# Power.net
KiCad netlist of a schematic drawn in Altium Designer
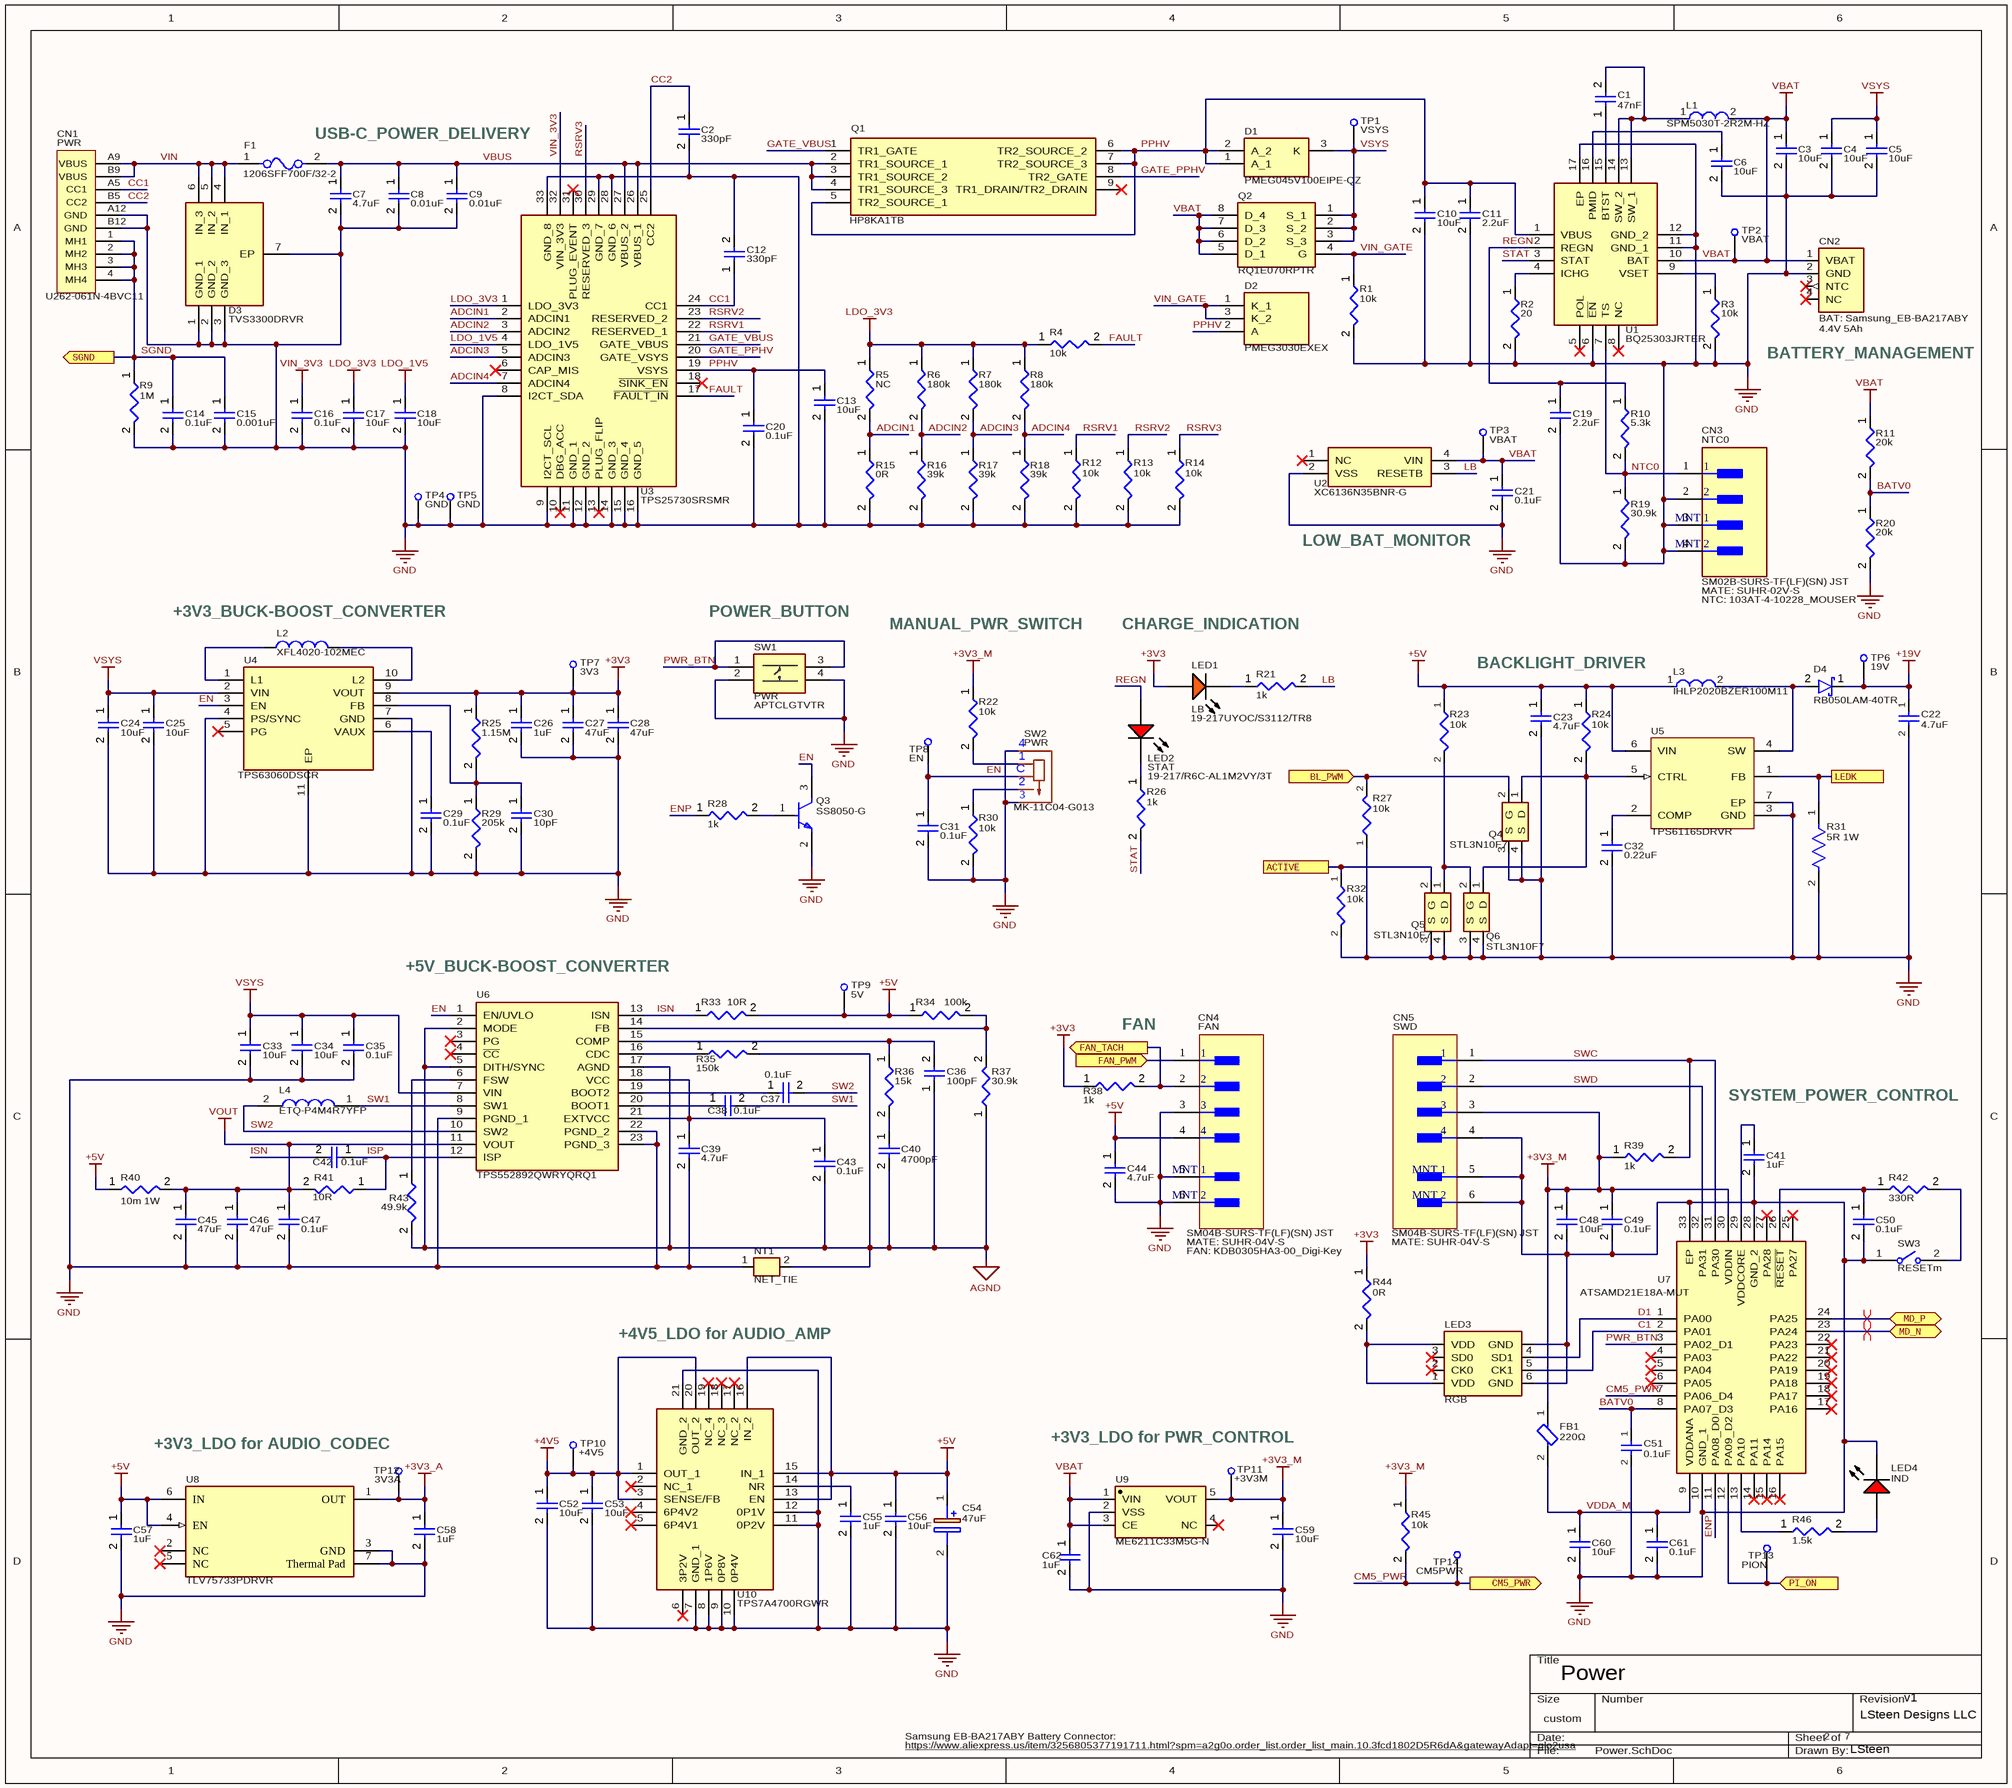
[diagram p0: Power.SchDoc]

(export (version "E")
  (design (tool "Eeschema 10.0.6"))
  (components
    (comp (ref "C1")
      (value "47nF")
      (footprint "CAPC1005X56X25LL10T15")
      (description "Chip Capacitor, 47 nF, +/- 5%, 16 V, 0402 (1005 Metric)")
      (fields (field (name "TOLERANCE") "5%"))
      (libsource (lib "Colorado Technical University") (part "CAP-NP-2"))
    )
    (comp (ref "C2")
      (value "330pF")
      (footprint "CAPC1005X56X25LL10T15")
      (description "Chip Capacitor, 330pF, +/- 5%, 16 V, 0402 (1005 Metric)")
      (fields (field (name "TOLERANCE") "5%"))
      (libsource (lib "Colorado Technical University") (part "CAP-NP-2"))
    )
    (comp (ref "C3")
      (value "10uF")
      (footprint "CAPC0805(2012)145_L")
      (description "Chip Capacitor, 10µF +/-20%, 25V, 0805, Thickness 1.45 mm")
      (fields (field (name "TOLERANCE") "10%"))
      (libsource (lib "Colorado Technical University") (part "CAP-NP-2"))
    )
    (comp (ref "C4")
      (value "10uF")
      (footprint "CAPC0805(2012)145_L")
      (description "Chip Capacitor, 10µF +/-20%, 25V, 0805, Thickness 1.45 mm")
      (fields (field (name "TOLERANCE") "10%"))
      (libsource (lib "Colorado Technical University") (part "CAP-NP-2"))
    )
    (comp (ref "C5")
      (value "10uF")
      (footprint "CAPC0805(2012)145_L")
      (description "Chip Capacitor, 10µF +/-20%, 25V, 0805, Thickness 1.45 mm")
      (fields (field (name "TOLERANCE") "10%"))
      (libsource (lib "Colorado Technical University") (part "CAP-NP-2"))
    )
    (comp (ref "C6")
      (value "10uF")
      (footprint "CAPC0805(2012)145_L")
      (description "Chip Capacitor, 10µF +/-20%, 25V, 0805, Thickness 1.45 mm")
      (fields (field (name "TOLERANCE") "10%"))
      (libsource (lib "Colorado Technical University") (part "CAP-NP-2"))
    )
    (comp (ref "C7")
      (value "4.7uF")
      (footprint "CAPC0603(1608)100_L")
      (description "Chip Capacitor, 4.7uF +/-20%, 10V, 0603, Thickness 1 mm")
      (fields (field (name "TOLERANCE") "10%"))
      (libsource (lib "Colorado Technical University") (part "CAP-NP-2"))
    )
    (comp (ref "C8")
      (value "0.01uF")
      (footprint "CAPC1005X56X25LL10T15")
      (description "Chip Capacitor, 0.01 uF, +/- 5%, 16 V, 0402 (1005 Metric)")
      (fields (field (name "TOLERANCE") "5%"))
      (libsource (lib "Colorado Technical University") (part "CAP-NP-2"))
    )
    (comp (ref "C9")
      (value "0.01uF")
      (footprint "CAPC1005X56X25LL10T15")
      (description "Chip Capacitor, 0.01 uF, +/- 5%, 16 V, 0402 (1005 Metric)")
      (fields (field (name "TOLERANCE") "5%"))
      (libsource (lib "Colorado Technical University") (part "CAP-NP-2"))
    )
    (comp (ref "C10")
      (value "10uF")
      (footprint "CAPC0805(2012)145_L")
      (description "Chip Capacitor, 10µF +/-20%, 25V, 0805, Thickness 1.45 mm")
      (fields (field (name "TOLERANCE") "10%"))
      (libsource (lib "Colorado Technical University") (part "CAP-NP-2"))
    )
    (comp (ref "C11")
      (value "2.2uF")
      (footprint "CAPC0603(1608)100_L")
      (description "Chip Capacitor, 2.2uF +/-20%, 10V, 0603, Thickness 1 mm")
      (fields (field (name "TOLERANCE") "10%"))
      (libsource (lib "Colorado Technical University") (part "CAP-NP-2"))
    )
    (comp (ref "C12")
      (value "330pF")
      (footprint "CAPC1005X56X25LL10T15")
      (description "Chip Capacitor, 330pF, +/- 5%, 16 V, 0402 (1005 Metric)")
      (fields (field (name "TOLERANCE") "5%"))
      (libsource (lib "Colorado Technical University") (part "CAP-NP-2"))
    )
    (comp (ref "C13")
      (value "10uF")
      (footprint "CAPC0603(1608)100_L")
      (description "Chip Capacitor, 10uF +/-20%, 10V, 0603, Thickness 1 mm")
      (fields (field (name "TOLERANCE") "10%"))
      (libsource (lib "Colorado Technical University") (part "CAP-NP-2"))
    )
    (comp (ref "C14")
      (value "0.1uF")
      (footprint "CAPC1005X56X25LL10T15")
      (description "Chip Capacitor, 0.1 uF, +/- 5%, 16 V, 0402 (1005 Metric)")
      (fields (field (name "TOLERANCE") "5%"))
      (libsource (lib "Colorado Technical University") (part "CAP-NP-2"))
    )
    (comp (ref "C15")
      (value "0.001uF")
      (footprint "CAPC1005X56X25LL10T15")
      (description "Chip Capacitor, 0.1 uF, +/- 5%, 16 V, 0402 (1005 Metric)")
      (fields (field (name "TOLERANCE") "5%"))
      (libsource (lib "Colorado Technical University") (part "CAP-NP-2"))
    )
    (comp (ref "C16")
      (value "0.1uF")
      (footprint "CAPC1005X56X25LL10T15")
      (description "Chip Capacitor, 0.1 uF, +/- 5%, 16 V, 0402 (1005 Metric)")
      (fields (field (name "TOLERANCE") "5%"))
      (libsource (lib "Colorado Technical University") (part "CAP-NP-2"))
    )
    (comp (ref "C17")
      (value "10uF")
      (footprint "CAPC0603(1608)100_L")
      (description "Chip Capacitor, 10uF +/-20%, 10V, 0603, Thickness 1 mm")
      (fields (field (name "TOLERANCE") "10%"))
      (libsource (lib "Colorado Technical University") (part "CAP-NP-2"))
    )
    (comp (ref "C18")
      (value "10uF")
      (footprint "CAPC0603(1608)100_L")
      (description "Chip Capacitor, 10uF +/-20%, 10V, 0603, Thickness 1 mm")
      (fields (field (name "TOLERANCE") "10%"))
      (libsource (lib "Colorado Technical University") (part "CAP-NP-2"))
    )
    (comp (ref "C19")
      (value "2.2uF")
      (footprint "CAPC1005X56X25LL10T15")
      (description "Chip Capacitor, 2.2uF uF, +/- 5%, 16 V, 0402 (1005 Metric)")
      (fields (field (name "TOLERANCE") "5%"))
      (libsource (lib "Colorado Technical University") (part "CAP-NP-2"))
    )
    (comp (ref "C20")
      (value "0.1uF")
      (footprint "CAPC1005X56X25LL10T15")
      (description "Chip Capacitor, 0.1 uF, +/- 5%, 16 V, 0402 (1005 Metric)")
      (fields (field (name "TOLERANCE") "5%"))
      (libsource (lib "Colorado Technical University") (part "CAP-NP-2"))
    )
    (comp (ref "C21")
      (value "0.1uF")
      (footprint "CAPC1005X56X25LL10T15")
      (description "Chip Capacitor, 0.1 uF, +/- 5%, 16 V, 0402 (1005 Metric)")
      (fields (field (name "TOLERANCE") "5%"))
      (libsource (lib "Colorado Technical University") (part "CAP-NP-2"))
    )
    (comp (ref "C22")
      (value "4.7uF")
      (footprint "SamacSys:CAPC2012X140N")
      (description "C0805")
      (libsource (lib "SamacSys") (part "C0805"))
    )
    (comp (ref "C23")
      (value "4.7uF")
      (footprint "CAPC0805(2012)145_L")
      (description "Chip Capacitor, 4.7µF +/-20%, 25V, 0805, Thickness 1.45 mm")
      (fields (field (name "TOLERANCE") "10%"))
      (libsource (lib "Colorado Technical University") (part "CAP-NP-2"))
    )
    (comp (ref "C24")
      (value "10uF")
      (footprint "CAPC0603(1608)100_L")
      (description "Chip Capacitor, 10uF +/-20%, 10V, 0603, Thickness 1 mm")
      (fields (field (name "TOLERANCE") "10%"))
      (libsource (lib "Colorado Technical University") (part "CAP-NP-2"))
    )
    (comp (ref "C25")
      (value "10uF")
      (footprint "CAPC0603(1608)100_L")
      (description "Chip Capacitor, 10uF +/-20%, 10V, 0603, Thickness 1 mm")
      (fields (field (name "TOLERANCE") "10%"))
      (libsource (lib "Colorado Technical University") (part "CAP-NP-2"))
    )
    (comp (ref "C26")
      (value "1uF")
      (footprint "CAPC1005X56X25LL10T15")
      (description "Chip Capacitor, 1 uF, +/- 5%, 16 V, 0402 (1005 Metric)")
      (fields (field (name "TOLERANCE") "5%"))
      (libsource (lib "Colorado Technical University") (part "CAP-NP-2"))
    )
    (comp (ref "C27")
      (value "47uF")
      (footprint "CAPC0805(2012)145_L")
      (description "Chip Capacitor, 47µF +/-20%, 25V, 0805, Thickness 1.45 mm")
      (fields (field (name "TOLERANCE") "10%"))
      (libsource (lib "Colorado Technical University") (part "CAP-NP-2"))
    )
    (comp (ref "C28")
      (value "47uF")
      (footprint "CAPC0805(2012)145_L")
      (description "Chip Capacitor, 47µF +/-20%, 25V, 0805, Thickness 1.45 mm")
      (fields (field (name "TOLERANCE") "10%"))
      (libsource (lib "Colorado Technical University") (part "CAP-NP-2"))
    )
    (comp (ref "C29")
      (value "0.1uF")
      (footprint "CAPC1005X56X25LL10T15")
      (description "Chip Capacitor, 0.1 uF, +/- 5%, 16 V, 0402 (1005 Metric)")
      (fields (field (name "TOLERANCE") "5%"))
      (libsource (lib "Colorado Technical University") (part "CAP-NP-2"))
    )
    (comp (ref "C30")
      (value "10pF")
      (footprint "CAPC1005X56X25LL10T15")
      (description "Chip Capacitor, 10 pF, +/- 5%, 16 V, 0402 (1005 Metric)")
      (fields (field (name "TOLERANCE") "5%"))
      (libsource (lib "Colorado Technical University") (part "CAP-NP-2"))
    )
    (comp (ref "C31")
      (value "0.1uF")
      (footprint "CAPC1005X56X25LL10T15")
      (description "Chip Capacitor, 0.1 uF, +/- 5%, 16 V, 0402 (1005 Metric)")
      (fields (field (name "TOLERANCE") "5%"))
      (libsource (lib "Colorado Technical University") (part "CAP-NP-2"))
    )
    (comp (ref "C32")
      (value "0.22uF")
      (footprint "CAPC1005X56X25LL10T15")
      (description "Chip Capacitor, 0.22 uF, +/- 5%, 16 V, 0402 (1005 Metric)")
      (fields (field (name "TOLERANCE") "5%"))
      (libsource (lib "Colorado Technical University") (part "CAP-NP-2"))
    )
    (comp (ref "C33")
      (value "10uF")
      (footprint "CAPC0805(2012)145_L")
      (description "Chip Capacitor, 10µF +/-20%, 25V, 0805, Thickness 1.45 mm")
      (fields (field (name "TOLERANCE") "10%"))
      (libsource (lib "Colorado Technical University") (part "CAP-NP-2"))
    )
    (comp (ref "C34")
      (value "10uF")
      (footprint "CAPC0805(2012)145_L")
      (description "Chip Capacitor, 10µF +/-20%, 25V, 0805, Thickness 1.45 mm")
      (fields (field (name "TOLERANCE") "10%"))
      (libsource (lib "Colorado Technical University") (part "CAP-NP-2"))
    )
    (comp (ref "C35")
      (value "0.1uF")
      (footprint "CAPC1005X56X25LL10T15")
      (description "Chip Capacitor, 0.1 uF, +/- 5%, 16 V, 0402 (1005 Metric)")
      (fields (field (name "TOLERANCE") "5%"))
      (libsource (lib "Colorado Technical University") (part "CAP-NP-2"))
    )
    (comp (ref "C36")
      (value "100pF")
      (footprint "CAPC1005X56X25LL10T15")
      (description "Chip Capacitor, 100 pF, +/- 5%, 16 V, 0402 (1005 Metric)")
      (fields (field (name "TOLERANCE") "5%"))
      (libsource (lib "Colorado Technical University") (part "CAP-NP-2"))
    )
    (comp (ref "C37")
      (value "0.1uF")
      (footprint "CAPC1005X56X25LL10T15")
      (description "Chip Capacitor, 0.1 uF, +/- 5%, 16 V, 0402 (1005 Metric)")
      (fields (field (name "TOLERANCE") "5%"))
      (libsource (lib "Colorado Technical University") (part "CAP-NP-2"))
    )
    (comp (ref "C38")
      (value "0.1uF")
      (footprint "CAPC1005X56X25LL10T15")
      (description "Chip Capacitor, 0.1 uF, +/- 5%, 16 V, 0402 (1005 Metric)")
      (fields (field (name "TOLERANCE") "5%"))
      (libsource (lib "Colorado Technical University") (part "CAP-NP-2"))
    )
    (comp (ref "C39")
      (value "4.7uF")
      (footprint "CAPC0603(1608)100_L")
      (description "Chip Capacitor, 4.7µF +/-20%, 10V, 0603, Thickness 1 mm")
      (fields (field (name "TOLERANCE") "10%"))
      (libsource (lib "Colorado Technical University") (part "CAP-NP-2"))
    )
    (comp (ref "C40")
      (value "4700pF")
      (footprint "CAPC1005X56X25LL10T15")
      (description "Chip Capacitor, 4700 pF, +/- 5%, 16 V, 0402 (1005 Metric)")
      (fields (field (name "TOLERANCE") "5%"))
      (libsource (lib "Colorado Technical University") (part "CAP-NP-2"))
    )
    (comp (ref "C41")
      (value "1uF")
      (footprint "CAPC1005X56X25LL10T15")
      (description "Chip Capacitor, 1 uF, +/- 5%, 16 V, 0402 (1005 Metric)")
      (fields (field (name "TOLERANCE") "5%"))
      (libsource (lib "Colorado Technical University") (part "CAP-NP-2"))
    )
    (comp (ref "C42")
      (value "0.1uF")
      (footprint "CAPC1005X56X25LL10T15")
      (description "Chip Capacitor, 0.1 uF, +/- 5%, 16 V, 0402 (1005 Metric)")
      (fields (field (name "TOLERANCE") "5%"))
      (libsource (lib "Colorado Technical University") (part "CAP-NP-2"))
    )
    (comp (ref "C43")
      (value "0.1uF")
      (footprint "CAPC1005X56X25LL10T15")
      (description "Chip Capacitor, 0.1 uF, +/- 5%, 16 V, 0402 (1005 Metric)")
      (fields (field (name "TOLERANCE") "5%"))
      (libsource (lib "Colorado Technical University") (part "CAP-NP-2"))
    )
    (comp (ref "C44")
      (value "4.7uF")
      (footprint "CAPC0805(2012)145_L")
      (description "Chip Capacitor, 4.7µF +/-20%, 25V, 0805, Thickness 1.45 mm")
      (fields (field (name "TOLERANCE") "10%"))
      (libsource (lib "Colorado Technical University") (part "CAP-NP-2"))
    )
    (comp (ref "C45")
      (value "47uF")
      (footprint "CAPC0805(2012)145_L")
      (description "Chip Capacitor, 47µF +/-40%, 6.3V, 0805, Thickness 1.45 mm")
      (fields (field (name "TOLERANCE") "10%"))
      (libsource (lib "Colorado Technical University") (part "CAP-NP-2"))
    )
    (comp (ref "C46")
      (value "47uF")
      (footprint "CAPC0805(2012)145_L")
      (description "Chip Capacitor, 47µF +/-40%, 6.3V, 0805, Thickness 1.45 mm")
      (fields (field (name "TOLERANCE") "10%"))
      (libsource (lib "Colorado Technical University") (part "CAP-NP-2"))
    )
    (comp (ref "C47")
      (value "0.1uF")
      (footprint "CAPC1005X56X25LL10T15")
      (description "Chip Capacitor, 0.1 uF, +/- 5%, 16 V, 0402 (1005 Metric)")
      (fields (field (name "TOLERANCE") "5%"))
      (libsource (lib "Colorado Technical University") (part "CAP-NP-2"))
    )
    (comp (ref "C48")
      (value "10uF")
      (footprint "CAPC0603(1608)100_L")
      (description "Chip Capacitor, 10uF +/-20%, 10V, 0603, Thickness 1 mm")
      (fields (field (name "TOLERANCE") "10%"))
      (libsource (lib "Colorado Technical University") (part "CAP-NP-2"))
    )
    (comp (ref "C49")
      (value "0.1uF")
      (footprint "CAPC1005X56X25LL10T15")
      (description "Chip Capacitor, 0.1 uF, +/- 5%, 16 V, 0402 (1005 Metric)")
      (fields (field (name "TOLERANCE") "5%"))
      (libsource (lib "Colorado Technical University") (part "CAP-NP-2"))
    )
    (comp (ref "C50")
      (value "0.1uF")
      (footprint "CAPC1005X56X25LL10T15")
      (description "Chip Capacitor, 0.1 uF, +/- 5%, 16 V, 0402 (1005 Metric)")
      (fields (field (name "TOLERANCE") "5%"))
      (libsource (lib "Colorado Technical University") (part "CAP-NP-2"))
    )
    (comp (ref "C51")
      (value "0.1uF")
      (footprint "SamacSys:CAPC1005X55N")
      (description "C0402")
      (libsource (lib "SamacSys") (part "C0402"))
    )
    (comp (ref "C52")
      (value "10uF")
      (footprint "CAPC0805(2012)145_L")
      (description "Chip Capacitor, 10µF +/-20%, 25V, 0805, Thickness 1.45 mm")
      (fields (field (name "TOLERANCE") "10%"))
      (libsource (lib "Colorado Technical University") (part "CAP-NP-2"))
    )
    (comp (ref "C53")
      (value "10uF")
      (footprint "CAPC0805(2012)145_L")
      (description "Chip Capacitor, 10µF +/-20%, 25V, 0805, Thickness 1.45 mm")
      (fields (field (name "TOLERANCE") "10%"))
      (libsource (lib "Colorado Technical University") (part "CAP-NP-2"))
    )
    (comp (ref "C54")
      (value "47uF")
      (footprint "SamacSys:CAPPM2014X140N")
      (description "Tantalum TLJR476M010R3200")
      (fields
        (field (name "MANUFACTURER_PART_NUMBER") "TLJR476M010R3200")
        (field (name "MOUSER PART NUMBER") "581-TLJR476M10R3200")
      )
      (libsource (lib "SamacSys") (part "TLJR476M010R3200"))
    )
    (comp (ref "C55")
      (value "1uF")
      (footprint "CAPC0603(1608)100_L")
      (description "Chip Capacitor, 1uF +/-20%, 10V, 0603, Thickness 1 mm")
      (fields (field (name "TOLERANCE") "10%"))
      (libsource (lib "Colorado Technical University") (part "CAP-NP-2"))
    )
    (comp (ref "C56")
      (value "10uF")
      (footprint "CAPC0805(2012)145_L")
      (description "Chip Capacitor, 10µF +/-20%, 25V, 0805, Thickness 1.45 mm")
      (fields (field (name "TOLERANCE") "10%"))
      (libsource (lib "Colorado Technical University") (part "CAP-NP-2"))
    )
    (comp (ref "C57")
      (value "1uF")
      (footprint "CAPC0603(1608)100_L")
      (description "Chip Capacitor, 1uF +/-20%, 10V, 0603, Thickness 1 mm")
      (fields (field (name "TOLERANCE") "10%"))
      (libsource (lib "Colorado Technical University") (part "CAP-NP-2"))
    )
    (comp (ref "C58")
      (value "1uF")
      (footprint "CAPC0603(1608)100_L")
      (description "Chip Capacitor, 1uF +/-20%, 10V, 0603, Thickness 1 mm")
      (fields (field (name "TOLERANCE") "10%"))
      (libsource (lib "Colorado Technical University") (part "CAP-NP-2"))
    )
    (comp (ref "C59")
      (value "10uF")
      (footprint "CAPC0603(1608)100_L")
      (description "Chip Capacitor, 10uF +/-20%, 10V, 0603, Thickness 1 mm")
      (fields (field (name "TOLERANCE") "10%"))
      (libsource (lib "Colorado Technical University") (part "CAP-NP-2"))
    )
    (comp (ref "C60")
      (value "10uF")
      (footprint "CAPC0603(1608)100_L")
      (description "Chip Capacitor, 10uF +/-20%, 10V, 0603, Thickness 1 mm")
      (fields (field (name "TOLERANCE") "10%"))
      (libsource (lib "Colorado Technical University") (part "CAP-NP-2"))
    )
    (comp (ref "C61")
      (value "0.1uF")
      (footprint "CAPC1005X56X25LL10T15")
      (description "Chip Capacitor, 0.1 uF, +/- 5%, 16 V, 0402 (1005 Metric)")
      (fields (field (name "TOLERANCE") "5%"))
      (libsource (lib "Colorado Technical University") (part "CAP-NP-2"))
    )
    (comp (ref "C62")
      (value "1uF")
      (footprint "CAPC0603(1608)100_L")
      (description "Chip Capacitor, 1uF +/-20%, 10V, 0603, Thickness 1 mm")
      (fields (field (name "TOLERANCE") "10%"))
      (libsource (lib "Colorado Technical University") (part "CAP-NP-2"))
    )
    (comp (ref "CN1")
      (value "PWR")
      (footprint "USB-SMD_U262-061N-4BVC11")
      (description "USB-C Connector")
      (fields
        (field (name "MANUFACTURER_PART_NUMBER") "U262-061N-4BVC11")
        (field (name "LCSC PART NUMBER") "C2764612")
      )
      (libsource (lib "Schlib1") (part "U262-061N-4BVC11"))
    )
    (comp (ref "CN2")
      (value "BAT")
      (footprint "BAT_SS_EB-BA217ABY_BRD")
      (description "Samsung battery connector")
      (libsource (lib "Schlib1") (part "BAT_SS_EB-BA217ABY_BRD"))
    )
    (comp (ref "CN3")
      (value "NTC0")
      (footprint "FP-SM02B-SURS-TF_LF_SN-MFG")
      (description "LCSC_CONN HEADER SMD R/A 2POS 0.8MM")
      (libsource (lib "Altium Content Vault") (part "6ebc6fc72a9fd5a6899c7600f385cff"))
    )
    (comp (ref "CN4")
      (value "FAN")
      (footprint "FP-SM04B-SURS-TF_LF_SN-MFG")
      (description "CONN HEADER SMD R/A 4POS 0.8MM")
      (libsource (lib "") (part "3b6f738a5616415d78381ad43816e4a_1"))
    )
    (comp (ref "CN5")
      (value "SWD")
      (footprint "FP-SM04B-SURS-TF_LF_SN-MFG")
      (description "CONN HEADER SMD R/A 4POS 0.8MM")
      (libsource (lib "Altium Content Vault") (part "3b6f738a5616415d78381ad43816e4a"))
    )
    (comp (ref "D1")
      (value "PMEG045V100EIPE-QZ")
      (footprint "SamacSys:PMEG045V100EIPEQZ")
      (description "Schottky Diode")
      (fields (field (name "MOUSER PART NUMBER") "771-MEG045V100EIPEQZ"))
      (libsource (lib "SamacSys") (part "PMEG045V100EIPE-QZ"))
    )
    (comp (ref "D2")
      (value "PMEG3030EXEX")
      (footprint "SamacSys:PMEG4010EXEX")
      (description "Schottky Diode")
      (libsource (lib "SamacSys") (part "PMEG3030EXEX"))
    )
    (comp (ref "D3")
      (value "TVS3300DRVR")
      (footprint "SamacSys:SON65P200X200X80-7N")
      (description "Integrated Circuit")
      (fields (field (name "MOUSER PART NUMBER") "595-TVS3300DRVR"))
      (libsource (lib "SamacSys") (part "TVS3300DRVR"))
    )
    (comp (ref "D4")
      (value "RB050LAM-40TR")
      (footprint "SamacSys:SODFL4725X105N")
      (description "Schottky Diode")
      (fields (field (name "MOUSER PART NUMBER") "755-RB050LAM-40TR"))
      (libsource (lib "SamacSys") (part "RB050LAM-40TR"))
    )
    (comp (ref "F1")
      (value "1206SFF700F/32-2")
      (footprint "FP-1206SFF-MFG")
      (description "FUSE BOARD MOUNT 7A 24VDC 1206")
      (fields
        (field (name "OCTOPART") "https://octopart.com/1206sff700f%2F32-2-littelfuse-74214425")
        (field (name "MANUFACTURER") "Littelfuse")
      )
      (libsource (lib "Altium Content Vault") (part "5bcf9b9f640e542cf0359d10258e979"))
    )
    (comp (ref "FB1")
      (value "220Ω")
      (footprint "FP-BLM18-0_15-t0_5-IPC_B")
      (description "Chip Ferrite Bead, 0603, 220Ω @ 100MHz, 25%, 0.04Ω, 2.5A")
      (libsource (lib "Altium Content Vault") (part "5f30dd21d616792df468990f7003faa"))
    )
    (comp (ref "L1")
      (value "SPM5030T-2R2M-HZ")
      (footprint "FP-SPM5030-MFG")
      (description "FIXED IND 2.2UH 8.5A 21.23 MOHM")
      (fields (field (name "TOLERANCE") "20%"))
      (libsource (lib "Altium Content Vault") (part "725321dda6339637d4d059423bc1c3c"))
    )
    (comp (ref "L2")
      (value "XFL4020-102MEC")
      (footprint "COIL-XFL4020_V")
      (description "Shielded Power Inductor, 1 uH, 64 MHz, -40 to 125 degC, 2-Pin SMD, RoHS, Tape and Reel")
      (fields (field (name "MANUFACTURER") "Coilcraft") (field (name "TOLERANCE") "20%"))
      (libsource (lib "Altium Content Vault") (part "IND-2"))
    )
    (comp (ref "L3")
      (value "IHLP2020BZER100M11")
      (footprint "FP-IHLP-2020BZ-FP_1_905x2-MFG")
      (description "Fixed Inductors Commercial Low DCR Series 10uH 2.2A 182.8mΩ 20%")
      (fields (field (name "TOLERANCE") "20%"))
      (libsource (lib "Altium Content Vault") (part "725321dda6339637d4d059423bc1c3c"))
    )
    (comp (ref "L4")
      (value "ETQ-P4M4R7YFP")
      (footprint "SamacSys:ETQP3M_4M_YFP")
      (description "Inductor")
      (fields (field (name "MOUSER PART NUMBER") "667-ETQ-P4M4R7YFP"))
      (libsource (lib "*") (part "ETQ-P4M4R7YFP"))
    )
    (comp (ref "LED1")
      (value "LB")
      (footprint "LED_0603")
      (fields (field (name "MPN") "19-217UYOC/S3112/TR8"))
      (libsource (lib "SamacSys") (part "19-217UYOC/S3112/TR8"))
    )
    (comp (ref "LED2")
      (value "STAT")
      (footprint "EVRL-0603-2_V")
      (description "Chip LED, Red, 5 V, 25 mA, -40 to 85 degC, 2-Pin SMD (0603), RoHS, Tape and Reel")
      (fields
        (field (name "MANUFACTURER") "Everlight Electronics")
        (field (name "MANUFACTURER PART NUMBER") "19-217/R6C-AL1M2VY/3T")
      )
      (libsource (lib "Altium Content Vault") (part "LED-RED-AK-2"))
    )
    (comp (ref "LED3")
      (value "RGB")
      (footprint "AP102-2020")
      (description "DotStar Micro RGB")
      (fields (field (name "MPN") "AP102-2020"))
      (libsource (lib "Schlib1") (part "AP102-2020"))
    )
    (comp (ref "LED4")
      (value "IND")
      (footprint "EVRL-0603-2_V")
      (description "Chip LED, Red, 5 V, 25 mA, -40 to 85 degC, 2-Pin SMD (0603), RoHS, Tape and Reel")
      (fields
        (field (name "MANUFACTURER") "Everlight Electronics")
        (field (name "MANUFACTURER PART NUMBER") "19-217/R6C-AL1M2VY/3T")
      )
      (libsource (lib "Altium Content Vault") (part "LED-RED-AK-2"))
    )
    (comp (ref "NT1") (value "NET_TIE") (footprint "NET_TIE1") (libsource (lib "Schlib1") (part "NET_TIE")))
    (comp (ref "Q1")
      (value "HP8KA1TB")
      (footprint "SamacSys:HP8KA1TB")
      (description "MOSFET (N-Channel)")
      (fields (field (name "MOUSER PART NUMBER") "755-HP8KA1TB"))
      (libsource (lib "*") (part "HP8KA1TB"))
    )
    (comp (ref "Q2")
      (value "RQ1E070RPTR")
      (footprint "SamacSys:RQ1E070RPTR")
      (description "MOSFET (P-Channel)")
      (fields (field (name "MOUSER PART NUMBER") "755-RQ1E070RPTR"))
      (libsource (lib "SamacSys") (part "RQ1E070RPTR"))
    )
    (comp (ref "Q3")
      (value "SS8050-G")
      (footprint "FP-SS8050-G-MFG")
      (description "NPN TRANSISTOR 1.5A 40V SOT-23 R")
      (libsource (lib "Altium Content Vault") (part "2a1388f82443b098dcd57d24ac7632d"))
    )
    (comp (ref "Q4")
      (value "STL3N10F7")
      (footprint "SamacSys:STL3N10F7")
      (description "MOSFET (N-Channel)")
      (fields (field (name "MOUSER PART NUMBER") "511-STL3N10F7"))
      (libsource (lib "SamacSys") (part "STL3N10F7"))
    )
    (comp (ref "Q5")
      (value "STL3N10F7")
      (footprint "SamacSys:STL3N10F7")
      (description "MOSFET (N-Channel)")
      (fields (field (name "MOUSER PART NUMBER") "511-STL3N10F7"))
      (libsource (lib "SamacSys") (part "STL3N10F7"))
    )
    (comp (ref "Q6")
      (value "STL3N10F7")
      (footprint "SamacSys:STL3N10F7")
      (description "MOSFET (N-Channel)")
      (fields (field (name "MOUSER PART NUMBER") "511-STL3N10F7"))
      (libsource (lib "SamacSys") (part "STL3N10F7"))
    )
    (comp (ref "R1")
      (value "10k")
      (footprint "RESC0402(1005)_L")
      (description "Chip Resistor, 10 kOhms, +/-5 %, 63 mW, -55 to 155 degC, 0402")
      (fields (field (name "TOLERANCE") "5%") (field (name "POWER") "63mW"))
      (libsource (lib "Colorado Technical University") (part "RES-2"))
    )
    (comp (ref "R2")
      (value "20")
      (footprint "RESC0402(1005)_L")
      (description "Chip Resistor, 20 kOhms, +/-5 %, 63 mW, -55 to 155 degC, 0402")
      (fields (field (name "TOLERANCE") "5%") (field (name "POWER") "63mW"))
      (libsource (lib "Colorado Technical University") (part "RES-2"))
    )
    (comp (ref "R3")
      (value "10k")
      (footprint "RESC0402(1005)_L")
      (description "Chip Resistor, 10 kOhms, +/-5 %, 63 mW, -55 to 155 degC, 0402")
      (fields (field (name "TOLERANCE") "5%") (field (name "POWER") "63mW"))
      (libsource (lib "Colorado Technical University") (part "RES-2"))
    )
    (comp (ref "R4")
      (value "10k")
      (footprint "RESC0402(1005)_L")
      (description "Chip Resistor, 10 kOhms, +/-5 %, 63 mW, -55 to 155 degC, 0402")
      (fields (field (name "TOLERANCE") "5%") (field (name "POWER") "63mW"))
      (libsource (lib "Colorado Technical University") (part "RES-2"))
    )
    (comp (ref "R5")
      (value "NC")
      (footprint "RESC0402(1005)_L")
      (description "Chip Resistor, NC, +/-5 %, 63 mW, -55 to 155 degC, 0402")
      (fields (field (name "TOLERANCE") "5%") (field (name "POWER") "63mW"))
      (libsource (lib "Colorado Technical University") (part "RES-2"))
    )
    (comp (ref "R6")
      (value "180k")
      (footprint "RESC0402(1005)_L")
      (description "Chip Resistor, 180 kOhms, +/-5 %, 63 mW, -55 to 155 degC, 0402")
      (fields (field (name "TOLERANCE") "5%") (field (name "POWER") "63mW"))
      (libsource (lib "Colorado Technical University") (part "RES-2"))
    )
    (comp (ref "R7")
      (value "180k")
      (footprint "RESC0402(1005)_L")
      (description "Chip Resistor, 180 kOhms, +/-5 %, 63 mW, -55 to 155 degC, 0402")
      (fields (field (name "TOLERANCE") "5%") (field (name "POWER") "63mW"))
      (libsource (lib "Colorado Technical University") (part "RES-2"))
    )
    (comp (ref "R8")
      (value "180k")
      (footprint "RESC0402(1005)_L")
      (description "Chip Resistor, 180 kOhms, +/-5 %, 63 mW, -55 to 155 degC, 0402")
      (fields (field (name "TOLERANCE") "5%") (field (name "POWER") "63mW"))
      (libsource (lib "Colorado Technical University") (part "RES-2"))
    )
    (comp (ref "R9")
      (value "1M")
      (footprint "RESC0402(1005)_L")
      (description "Chip Resistor, 1 MOhms, +/-5 %, 63 mW, -55 to 155 degC, 0402")
      (fields (field (name "TOLERANCE") "5%") (field (name "POWER") "63mW"))
      (libsource (lib "Colorado Technical University") (part "RES-2"))
    )
    (comp (ref "R10")
      (value "5.3k")
      (footprint "RESC0402(1005)_L")
      (description "Chip Resistor, 5.3 kOhms, +/-5 %, 63 mW, -55 to 155 degC, 0402")
      (fields (field (name "TOLERANCE") "5%") (field (name "POWER") "63mW"))
      (libsource (lib "Colorado Technical University") (part "RES-2"))
    )
    (comp (ref "R11")
      (value "20k")
      (footprint "RESC0402(1005)_L")
      (description "Chip Resistor, 40 kOhms, +/-5 %, 63 mW, -55 to 155 degC, 0402")
      (fields (field (name "TOLERANCE") "5%") (field (name "POWER") "63mW"))
      (libsource (lib "Colorado Technical University") (part "RES-2"))
    )
    (comp (ref "R12")
      (value "10k")
      (footprint "RESC0402(1005)_L")
      (description "Chip Resistor, 10 kOhms, +/-5 %, 63 mW, -55 to 155 degC, 0402")
      (fields (field (name "TOLERANCE") "5%") (field (name "POWER") "63mW"))
      (libsource (lib "Colorado Technical University") (part "RES-2"))
    )
    (comp (ref "R13")
      (value "10k")
      (footprint "RESC0402(1005)_L")
      (description "Chip Resistor, 10 kOhms, +/-5 %, 63 mW, -55 to 155 degC, 0402")
      (fields (field (name "TOLERANCE") "5%") (field (name "POWER") "63mW"))
      (libsource (lib "Colorado Technical University") (part "RES-2"))
    )
    (comp (ref "R14")
      (value "10k")
      (footprint "RESC0402(1005)_L")
      (description "Chip Resistor, 10 kOhms, +/-5 %, 63 mW, -55 to 155 degC, 0402")
      (fields (field (name "TOLERANCE") "5%") (field (name "POWER") "63mW"))
      (libsource (lib "Colorado Technical University") (part "RES-2"))
    )
    (comp (ref "R15")
      (value "0R")
      (footprint "RESC0402(1005)_L")
      (description "Chip Resistor, 0 Ohms, +/-5 %, 63 mW, -55 to 155 degC, 0402")
      (fields (field (name "TOLERANCE") "5%") (field (name "POWER") "63mW"))
      (libsource (lib "Colorado Technical University") (part "RES-2"))
    )
    (comp (ref "R16")
      (value "39k")
      (footprint "RESC0402(1005)_L")
      (description "Chip Resistor, 39 kOhms, +/-5 %, 63 mW, -55 to 155 degC, 0402")
      (fields (field (name "TOLERANCE") "5%") (field (name "POWER") "63mW"))
      (libsource (lib "Colorado Technical University") (part "RES-2"))
    )
    (comp (ref "R17")
      (value "39k")
      (footprint "RESC0402(1005)_L")
      (description "Chip Resistor, 39 kOhms, +/-5 %, 63 mW, -55 to 155 degC, 0402")
      (fields (field (name "TOLERANCE") "5%") (field (name "POWER") "63mW"))
      (libsource (lib "Colorado Technical University") (part "RES-2"))
    )
    (comp (ref "R18")
      (value "39k")
      (footprint "RESC0402(1005)_L")
      (description "Chip Resistor, 39 kOhms, +/-5 %, 63 mW, -55 to 155 degC, 0402")
      (fields (field (name "TOLERANCE") "5%") (field (name "POWER") "63mW"))
      (libsource (lib "Colorado Technical University") (part "RES-2"))
    )
    (comp (ref "R19")
      (value "30.9k")
      (footprint "RESC0402(1005)_L")
      (description "Chip Resistor, 30.9 kOhms, +/-5 %, 63 mW, -55 to 155 degC, 0402")
      (fields (field (name "TOLERANCE") "5%") (field (name "POWER") "63mW"))
      (libsource (lib "Colorado Technical University") (part "RES-2"))
    )
    (comp (ref "R20")
      (value "20k")
      (footprint "RESC0402(1005)_L")
      (description "Chip Resistor, 40 kOhms, +/-5 %, 63 mW, -55 to 155 degC, 0402")
      (fields (field (name "TOLERANCE") "5%") (field (name "POWER") "63mW"))
      (libsource (lib "Colorado Technical University") (part "RES-2"))
    )
    (comp (ref "R21")
      (value "1k")
      (footprint "RESC0402(1005)_L")
      (description "Chip Resistor, 1 kOhms, +/-5 %, 63 mW, -55 to 155 degC, 0402")
      (fields (field (name "TOLERANCE") "5%") (field (name "POWER") "63mW"))
      (libsource (lib "Colorado Technical University") (part "RES-2"))
    )
    (comp (ref "R22")
      (value "10k")
      (footprint "RESC0402(1005)_L")
      (description "Chip Resistor, 10 kOhms, +/-5 %, 63 mW, -55 to 155 degC, 0402")
      (fields (field (name "TOLERANCE") "5%") (field (name "POWER") "63mW"))
      (libsource (lib "Colorado Technical University") (part "RES-2"))
    )
    (comp (ref "R23")
      (value "10k")
      (footprint "SamacSys:ERA2AED122X")
      (description "R0402")
      (libsource (lib "SamacSys") (part "R0402"))
    )
    (comp (ref "R24")
      (value "10k")
      (footprint "RESC0402(1005)_L")
      (description "Chip Resistor, 10 kOhms, +/-5 %, 63 mW, -55 to 155 degC, 0402")
      (fields (field (name "TOLERANCE") "5%") (field (name "POWER") "63mW"))
      (libsource (lib "Colorado Technical University") (part "RES-2"))
    )
    (comp (ref "R25")
      (value "1.15M")
      (footprint "RESC0402(1005)_L")
      (description "Chip Resistor, 1.15 MOhms, +/-5 %, 63 mW, -55 to 155 degC, 0402")
      (fields (field (name "TOLERANCE") "5%") (field (name "POWER") "63mW"))
      (libsource (lib "Colorado Technical University") (part "RES-2"))
    )
    (comp (ref "R26")
      (value "1k")
      (footprint "RESC0402(1005)_L")
      (description "Chip Resistor, 1 kOhms, +/-5 %, 63 mW, -55 to 155 degC, 0402")
      (fields (field (name "TOLERANCE") "5%") (field (name "POWER") "63mW"))
      (libsource (lib "Colorado Technical University") (part "RES-2"))
    )
    (comp (ref "R27")
      (value "10k")
      (footprint "SamacSys:ERA2AED122X")
      (description "R0402")
      (libsource (lib "SamacSys") (part "R0402"))
    )
    (comp (ref "R28")
      (value "1k")
      (footprint "RESC0402(1005)_L")
      (description "Chip Resistor, 1 kOhms, +/-5 %, 63 mW, -55 to 155 degC, 0402")
      (fields (field (name "TOLERANCE") "5%") (field (name "POWER") "63mW"))
      (libsource (lib "Colorado Technical University") (part "RES-2"))
    )
    (comp (ref "R29")
      (value "205k")
      (footprint "RESC0402(1005)_L")
      (description "Chip Resistor, 205 kOhms, +/-5 %, 63 mW, -55 to 155 degC, 0402")
      (fields (field (name "TOLERANCE") "5%") (field (name "POWER") "63mW"))
      (libsource (lib "Colorado Technical University") (part "RES-2"))
    )
    (comp (ref "R30")
      (value "10k")
      (footprint "RESC0402(1005)_L")
      (description "Chip Resistor, 10 kOhms, +/-5 %, 63 mW, -55 to 155 degC, 0402")
      (fields (field (name "TOLERANCE") "5%") (field (name "POWER") "63mW"))
      (libsource (lib "Colorado Technical University") (part "RES-2"))
    )
    (comp (ref "R31")
      (value "5R 1W")
      (footprint "FP-CRCW2512-e3-MFG")
      (description "RES Thick Film, 5.49Ω, 1%, 1W, 100ppm/°C, 2512")
      (fields (field (name "TOLERANCE") "1%") (field (name "MPN") "HoAR2512-1W-5R-0.1%-TCR25"))
      (libsource (lib "Altium Content Vault") (part "1029c3af85768c4190bb7ad29bc67b5"))
    )
    (comp (ref "R32")
      (value "10k")
      (footprint "SamacSys:ERA2AED122X")
      (description "R0402")
      (libsource (lib "SamacSys") (part "R0402"))
    )
    (comp (ref "R33")
      (value "10R")
      (footprint "RESC0402(1005)_L")
      (description "Chip Resistor, 10 Ohms, +/-5 %, 63 mW, -55 to 155 degC, 0402")
      (fields (field (name "TOLERANCE") "5%") (field (name "POWER") "63mW"))
      (libsource (lib "Colorado Technical University") (part "RES-2"))
    )
    (comp (ref "R34")
      (value "100k")
      (footprint "RESC0402(1005)_L")
      (description "Chip Resistor, 100 kOhms, +/-5 %, 63 mW, -55 to 155 degC, 0402")
      (fields (field (name "TOLERANCE") "5%") (field (name "POWER") "63mW"))
      (libsource (lib "Colorado Technical University") (part "RES-2"))
    )
    (comp (ref "R35")
      (value "150k")
      (footprint "RESC0402(1005)_L")
      (description "Chip Resistor, 150 kOhms, +/-5 %, 63 mW, -55 to 155 degC, 0402")
      (fields (field (name "TOLERANCE") "5%") (field (name "POWER") "63mW"))
      (libsource (lib "Colorado Technical University") (part "RES-2"))
    )
    (comp (ref "R36")
      (value "15k")
      (footprint "RESC0402(1005)_L")
      (description "Chip Resistor, 15 kOhms, +/-5 %, 63 mW, -55 to 155 degC, 0402")
      (fields (field (name "TOLERANCE") "5%") (field (name "POWER") "63mW"))
      (libsource (lib "Colorado Technical University") (part "RES-2"))
    )
    (comp (ref "R37")
      (value "30.9k")
      (footprint "RESC0402(1005)_L")
      (description "Chip Resistor, 30.9 kOhms, +/-5 %, 63 mW, -55 to 155 degC, 0402")
      (fields (field (name "TOLERANCE") "5%") (field (name "POWER") "63mW"))
      (libsource (lib "Colorado Technical University") (part "RES-2"))
    )
    (comp (ref "R38")
      (value "1k")
      (footprint "RESC0402(1005)_L")
      (description "Chip Resistor, 1 kOhms, +/-5 %, 63 mW, -55 to 155 degC, 0402")
      (fields (field (name "TOLERANCE") "5%") (field (name "POWER") "63mW"))
      (libsource (lib "Colorado Technical University") (part "RES-2"))
    )
    (comp (ref "R39")
      (value "1k")
      (footprint "RESC0402(1005)_L")
      (description "Chip Resistor, 1 kOhms, +/-5 %, 63 mW, -55 to 155 degC, 0402")
      (fields (field (name "TOLERANCE") "5%") (field (name "POWER") "63mW"))
      (libsource (lib "Colorado Technical University") (part "RES-2"))
    )
    (comp (ref "R40")
      (value "10m 1W")
      (footprint "RESC3216X60X45ML15T20")
      (description "Chip Resistor, 10 mOhm, +/- 1%, 0.25 W, -55 to 155 degC, 1206 (3216 Metric)")
      (fields (field (name "TOLERANCE") "1%") (field (name "POWER") "1W"))
      (libsource (lib "Colorado Technical University") (part "RES-2"))
    )
    (comp (ref "R41")
      (value "10R")
      (footprint "RESC0402(1005)_L")
      (description "Chip Resistor, 10 Ohms, +/-5 %, 63 mW, -55 to 155 degC, 0402")
      (fields (field (name "TOLERANCE") "5%") (field (name "POWER") "63mW"))
      (libsource (lib "Colorado Technical University") (part "RES-2"))
    )
    (comp (ref "R42")
      (value "330R")
      (footprint "RESC0402(1005)_L")
      (description "Chip Resistor, 330 Ohms, +/-5 %, 63 mW, -55 to 155 degC, 0402")
      (fields (field (name "TOLERANCE") "5%") (field (name "POWER") "63mW"))
      (libsource (lib "Colorado Technical University") (part "RES-2"))
    )
    (comp (ref "R43")
      (value "49.9k")
      (footprint "RESC0402(1005)_L")
      (description "Chip Resistor, 49.9 kOhms, +/-5 %, 63 mW, -55 to 155 degC, 0402")
      (fields (field (name "TOLERANCE") "5%") (field (name "POWER") "63mW"))
      (libsource (lib "Colorado Technical University") (part "RES-2"))
    )
    (comp (ref "R44")
      (value "0R")
      (footprint "RESC0402(1005)_L")
      (description "Chip Resistor, 0 Ohms, +/-5 %, 63 mW, -55 to 155 degC, 0402")
      (fields (field (name "TOLERANCE") "5%") (field (name "POWER") "63mW"))
      (libsource (lib "Colorado Technical University") (part "RES-2"))
    )
    (comp (ref "R45")
      (value "10k")
      (footprint "RESC0402(1005)_L")
      (description "Chip Resistor, 10 kOhms, +/-5 %, 63 mW, -55 to 155 degC, 0402")
      (fields (field (name "TOLERANCE") "5%") (field (name "POWER") "63mW"))
      (libsource (lib "Colorado Technical University") (part "RES-2"))
    )
    (comp (ref "R46")
      (value "1.5k")
      (footprint "RESC0402(1005)_L")
      (description "Chip Resistor, 1.5 kOhms, +/-5 %, 63 mW, -55 to 155 degC, 0402")
      (fields (field (name "TOLERANCE") "5%") (field (name "POWER") "63mW"))
      (libsource (lib "Colorado Technical University") (part "RES-2"))
    )
    (comp (ref "SW1")
      (value "PWR")
      (footprint "SamacSys:APTCLGTVTR")
      (description "Switch")
      (fields
        (field (name "MANUFACTURER_PART_NUMBER") "APTCLGTVTR")
        (field (name "MOUSER PART NUMBER") "642-APTCLGTVTR")
      )
      (libsource (lib "SamacSys") (part "APTCLGTVTR"))
    )
    (comp (ref "SW2")
      (value "PWR")
      (footprint "SW-SMD_MK-11C04-G013")
      (description "SPDT 1A 6V Slide Switch")
      (libsource (lib "Schlib1") (part "MK-11C04-G013"))
    )
    (comp (ref "SW3")
      (value "RESETm")
      (footprint "FP-B3U-1000P-MFG")
      (description "LCSC SWITCH TACTILE SPST-NO 0.05A 12V")
      (libsource (lib "Altium Content Vault") (part "ae622034201233ca1abcedc05908f33"))
    )
    (comp (ref "TP1")
      (value "VSYS")
      (footprint "TP")
      (description "TestPoint")
      (libsource (lib "Schlib1") (part "TestPoint"))
    )
    (comp (ref "TP2")
      (value "VBAT")
      (footprint "TP")
      (description "TestPoint")
      (libsource (lib "Schlib1") (part "TestPoint"))
    )
    (comp (ref "TP3")
      (value "VBAT")
      (footprint "TP")
      (description "TestPoint")
      (libsource (lib "Schlib1") (part "TestPoint"))
    )
    (comp (ref "TP4")
      (value "GND")
      (footprint "TP")
      (description "TestPoint")
      (libsource (lib "Schlib1") (part "TestPoint"))
    )
    (comp (ref "TP5")
      (value "GND")
      (footprint "TP")
      (description "TestPoint")
      (libsource (lib "Schlib1") (part "TestPoint"))
    )
    (comp (ref "TP6")
      (value "19V")
      (footprint "TP")
      (description "TestPoint")
      (libsource (lib "Schlib1") (part "TestPoint"))
    )
    (comp (ref "TP7")
      (value "3V3")
      (footprint "TP")
      (description "TestPoint")
      (libsource (lib "Schlib1") (part "TestPoint"))
    )
    (comp (ref "TP8")
      (value "EN")
      (footprint "TP")
      (description "TestPoint")
      (libsource (lib "Schlib1") (part "TestPoint"))
    )
    (comp (ref "TP9")
      (value "5V")
      (footprint "TP")
      (description "TestPoint")
      (libsource (lib "Schlib1") (part "TestPoint"))
    )
    (comp (ref "TP10")
      (value "+4V5")
      (footprint "TP")
      (description "TestPoint")
      (libsource (lib "Schlib1") (part "TestPoint"))
    )
    (comp (ref "TP11")
      (value "+3V3M")
      (footprint "TP")
      (description "TestPoint")
      (libsource (lib "Schlib1") (part "TestPoint"))
    )
    (comp (ref "TP12")
      (value "3V3A")
      (footprint "TP")
      (description "TestPoint")
      (libsource (lib "Schlib1") (part "TestPoint"))
    )
    (comp (ref "TP13")
      (value "PION")
      (footprint "TP")
      (description "TestPoint")
      (libsource (lib "Schlib1") (part "TestPoint"))
    )
    (comp (ref "TP14")
      (value "CM5PWR")
      (footprint "TP")
      (description "TestPoint")
      (libsource (lib "Schlib1") (part "TestPoint"))
    )
    (comp (ref "U1")
      (value "BQ25303JRTER")
      (footprint "SamacSys:QFN50P300X300X80-17N-D")
      (description "Integrated Circuit")
      (fields (field (name "MOUSER PART NUMBER") "595-BQ25303JRTER"))
      (libsource (lib "*") (part "BQ25303JRTER"))
    )
    (comp (ref "U2")
      (value "XC6136N35BNR-G")
      (footprint "SamacSys:XC6136C12ANRG")
      (description "Integrated Circuit")
      (fields (field (name "MOUSER PART NUMBER") "865-XC6136N35BNR-G"))
      (libsource (lib "SamacSys") (part "XC6136N35BNR-G"))
    )
    (comp (ref "U3")
      (value "TPS25730SRSMR")
      (footprint "QFN40P400X400X100-33N-D")
      (description "Integrated Circuit")
      (fields (field (name "MOUSER PART NUMBER") "595-TPS25730SRSMR"))
      (libsource (lib "SamacSys") (part "TPS25730SRSMR"))
    )
    (comp (ref "U4")
      (value "TPS63060DSCR")
      (footprint "SamacSys:SON50P300X300X80-11N-D")
      (description "Integrated Circuit")
      (fields (field (name "MOUSER PART NUMBER") "595-TPS63060DSCR"))
      (libsource (lib "SamacSys") (part "TPS63060DSCR"))
    )
    (comp (ref "U5")
      (value "TPS61165DRVR")
      (footprint "DRV0006A_V")
      (fields (field (name "MANUFACTURER") "Texas Instruments"))
      (libsource (lib "Altium Content Vault") (part "TI-TPS6116XDRV6-1600X1000TP"))
    )
    (comp (ref "U6")
      (value "TPS552892QWRYQRQ1")
      (footprint "SamacSys:TPS552892QWRYQRQ1")
      (description "Integrated Circuit")
      (fields (field (name "MOUSER PART NUMBER") "595-PS552892QWRYQRQ1"))
      (libsource (lib "*") (part "TPS552892QWRYQRQ1"))
    )
    (comp (ref "U7")
      (value "ATSAMD21E18A-MUT")
      (footprint "SamacSys:QFN50P500X500X90-33N-D")
      (description "Integrated Circuit")
      (fields (field (name "MOUSER PART NUMBER") "556-ATSAMD21E18A-MUT"))
      (libsource (lib "SamacSys") (part "ATSAMD21E18A-MUT"))
    )
    (comp (ref "U8")
      (value "TLV75733PDRVR")
      (footprint "FP-DRV0006A-IPC_B")
      (description "IC REG LINEAR 3.3V 1A 6WSON")
      (libsource (lib "Altium Content Vault") (part "0b05c65f2e02c79b80966f21e07e3b1"))
    )
    (comp (ref "U9")
      (value "ME6211C33M5G-N")
      (footprint "SOT95P270X145-5N")
      (description "LCSC +3.3V LDO 500mA VDIF=120mV@100mA")
      (libsource (lib "Schlib1") (part "ME6211C33M5G-N"))
    )
    (comp (ref "U10")
      (value "TPS7A4700RGWR")
      (footprint "SamacSys:QFN65P500X500X100-21N-D")
      (description "Integrated Circuit")
      (fields (field (name "MOUSER PART NUMBER") "595-TPS7A4700RGWR"))
      (libsource (lib "SamacSys") (part "TPS7A4700RGWR"))
    )
  )
  (nets
    (net (code "1") (name "+3V3") (class "Default")
      (node (ref "C26") (pin "1") (pinfunction "1_1") (pintype "passive"))
      (node (ref "C27") (pin "1") (pinfunction "1_1") (pintype "passive"))
      (node (ref "C28") (pin "1") (pinfunction "1_1") (pintype "passive"))
      (node (ref "LED1") (pin "1") (pinfunction "A_1") (pintype "passive"))
      (node (ref "R25") (pin "1") (pinfunction "1_1") (pintype "passive"))
      (node (ref "R38") (pin "1") (pinfunction "1_1") (pintype "passive"))
      (node (ref "R44") (pin "1") (pinfunction "1_1") (pintype "passive"))
      (node (ref "TP7") (pin "1") (pinfunction "1_1") (pintype "passive"))
      (node (ref "U4") (pin "9") (pinfunction "VOUT_9") (pintype "passive"))
    )
    (net (code "2") (name "+3V3_A") (class "Default")
      (node (ref "C58") (pin "1") (pinfunction "1_1") (pintype "passive"))
      (node (ref "TP12") (pin "1") (pinfunction "1_1") (pintype "passive"))
      (node (ref "U8") (pin "1") (pinfunction "OUT_1") (pintype "power_in"))
    )
    (net (code "3") (name "+3V3_M") (class "Default")
      (node (ref "C48") (pin "1") (pinfunction "1_1") (pintype "passive"))
      (node (ref "C49") (pin "1") (pinfunction "1_1") (pintype "passive"))
      (node (ref "C59") (pin "1") (pinfunction "1_1") (pintype "passive"))
      (node (ref "CN5") (pin "3") (pinfunction "3_3") (pintype "passive"))
      (node (ref "FB1") (pin "1") (pinfunction "1_1") (pintype "passive"))
      (node (ref "R22") (pin "1") (pinfunction "1_1") (pintype "passive"))
      (node (ref "R39") (pin "1") (pinfunction "1_1") (pintype "passive"))
      (node (ref "R45") (pin "1") (pinfunction "1_1") (pintype "passive"))
      (node (ref "TP11") (pin "1") (pinfunction "1_1") (pintype "passive"))
      (node (ref "U7") (pin "30") (pinfunction "VDDIN_30") (pintype "passive"))
      (node (ref "U9") (pin "5") (pinfunction "VOUT_5") (pintype "passive"))
    )
    (net (code "4") (name "+4V5") (class "Default")
      (node (ref "C52") (pin "1") (pinfunction "1_1") (pintype "passive"))
      (node (ref "C53") (pin "1") (pinfunction "1_1") (pintype "passive"))
      (node (ref "TP10") (pin "1") (pinfunction "1_1") (pintype "passive"))
      (node (ref "U10") (pin "1") (pinfunction "OUT_1_1") (pintype "passive"))
      (node (ref "U10") (pin "20") (pinfunction "OUT_2_20") (pintype "passive"))
      (node (ref "U10") (pin "3") (pinfunction "SENSE/FB_3") (pintype "passive"))
    )
    (net (code "5") (name "+5V") (class "Default")
      (node (ref "C23") (pin "1") (pinfunction "1_1") (pintype "passive"))
      (node (ref "C44") (pin "1") (pinfunction "1_1") (pintype "passive"))
      (node (ref "C54") (pin "1") (pinfunction "+_1") (pintype "passive"))
      (node (ref "C56") (pin "1") (pinfunction "1_1") (pintype "passive"))
      (node (ref "C57") (pin "1") (pinfunction "1_1") (pintype "passive"))
      (node (ref "CN4") (pin "4") (pinfunction "4_4") (pintype "passive"))
      (node (ref "L3") (pin "1") (pinfunction "1_1") (pintype "passive"))
      (node (ref "R23") (pin "1") (pinfunction "1_1") (pintype "passive"))
      (node (ref "R24") (pin "1") (pinfunction "1_1") (pintype "passive"))
      (node (ref "R33") (pin "2") (pinfunction "2_2") (pintype "passive"))
      (node (ref "R34") (pin "1") (pinfunction "1_1") (pintype "passive"))
      (node (ref "R40") (pin "1") (pinfunction "1_1") (pintype "passive"))
      (node (ref "TP9") (pin "1") (pinfunction "1_1") (pintype "passive"))
      (node (ref "U10") (pin "13") (pinfunction "EN_13") (pintype "passive"))
      (node (ref "U10") (pin "15") (pinfunction "IN_1_15") (pintype "passive"))
      (node (ref "U10") (pin "16") (pinfunction "IN_2_16") (pintype "passive"))
      (node (ref "U5") (pin "6") (pinfunction "VIN_6") (pintype "power_in"))
      (node (ref "U8") (pin "4") (pinfunction "EN_4") (pintype "input"))
      (node (ref "U8") (pin "6") (pinfunction "IN_6") (pintype "power_in"))
    )
    (net (code "6") (name "+19V") (class "Default")
      (node (ref "C22") (pin "1") (pinfunction "1_1") (pintype "passive"))
      (node (ref "D4") (pin "1") (pinfunction "1_1") (pintype "passive"))
      (node (ref "TP6") (pin "1") (pinfunction "1_1") (pintype "passive"))
    )
    (net (code "7") (name "/ACTIVE") (class "Default")
      (node (ref "Q5") (pin "2") (pinfunction "G_2") (pintype "passive"))
      (node (ref "R32") (pin "1") (pinfunction "1_1") (pintype "passive"))
    )
    (net (code "8") (name "/ADCIN1") (class "Default")
      (node (ref "R15") (pin "1") (pinfunction "1_1") (pintype "passive"))
      (node (ref "R5") (pin "2") (pinfunction "2_2") (pintype "passive"))
      (node (ref "U3") (pin "2") (pinfunction "ADCIN1_2") (pintype "passive"))
    )
    (net (code "9") (name "/ADCIN2") (class "Default")
      (node (ref "R16") (pin "1") (pinfunction "1_1") (pintype "passive"))
      (node (ref "R6") (pin "2") (pinfunction "2_2") (pintype "passive"))
      (node (ref "U3") (pin "3") (pinfunction "ADCIN2_3") (pintype "passive"))
    )
    (net (code "10") (name "/ADCIN3") (class "Default")
      (node (ref "R17") (pin "1") (pinfunction "1_1") (pintype "passive"))
      (node (ref "R7") (pin "2") (pinfunction "2_2") (pintype "passive"))
      (node (ref "U3") (pin "5") (pinfunction "ADCIN3_5") (pintype "passive"))
    )
    (net (code "11") (name "/ADCIN4") (class "Default")
      (node (ref "R18") (pin "1") (pinfunction "1_1") (pintype "passive"))
      (node (ref "R8") (pin "2") (pinfunction "2_2") (pintype "passive"))
      (node (ref "U3") (pin "7") (pinfunction "ADCIN4_7") (pintype "passive"))
    )
    (net (code "12") (name "/BATV0") (class "Default")
      (node (ref "C51") (pin "1") (pinfunction "1_1") (pintype "passive"))
      (node (ref "R11") (pin "2") (pinfunction "2_2") (pintype "passive"))
      (node (ref "R20") (pin "1") (pinfunction "1_1") (pintype "passive"))
      (node (ref "U7") (pin "8") (pinfunction "PA07_D3_8") (pintype "passive"))
    )
    (net (code "13") (name "/BL_PWM") (class "Default")
      (node (ref "Q4") (pin "2") (pinfunction "G_2") (pintype "passive"))
      (node (ref "R27") (pin "2") (pinfunction "2_2") (pintype "passive"))
    )
    (net (code "14") (name "/C1") (class "Default")
      (node (ref "LED3") (pin "5") (pinfunction "CK1_5") (pintype "passive"))
      (node (ref "U7") (pin "2") (pinfunction "PA01_2") (pintype "passive"))
    )
    (net (code "15") (name "/CC1") (class "Default")
      (node (ref "C12") (pin "1") (pinfunction "1_1") (pintype "passive"))
      (node (ref "CN1") (pin "A5") (pinfunction "CC1_A5") (pintype "passive"))
      (node (ref "U3") (pin "24") (pinfunction "CC1_24") (pintype "passive"))
    )
    (net (code "16") (name "/CC2") (class "Default")
      (node (ref "C2") (pin "1") (pinfunction "1_1") (pintype "passive"))
      (node (ref "CN1") (pin "B5") (pinfunction "CC2_B5") (pintype "passive"))
      (node (ref "U3") (pin "25") (pinfunction "CC2_25") (pintype "passive"))
    )
    (net (code "17") (name "/CM5_PWR") (class "Default")
      (node (ref "R45") (pin "2") (pinfunction "2_2") (pintype "passive"))
      (node (ref "TP14") (pin "1") (pinfunction "1_1") (pintype "passive"))
      (node (ref "U7") (pin "7") (pinfunction "PA06_D4_7") (pintype "passive"))
    )
    (net (code "18") (name "/D1") (class "Default")
      (node (ref "LED3") (pin "4") (pinfunction "SD1_4") (pintype "passive"))
      (node (ref "U7") (pin "1") (pinfunction "PA00_1") (pintype "passive"))
    )
    (net (code "19") (name "/EN") (class "Default")
      (node (ref "C31") (pin "1") (pinfunction "1_1") (pintype "passive"))
      (node (ref "Q3") (pin "3") (pinfunction "C_3") (pintype "passive"))
      (node (ref "SW2") (pin "C") (pinfunction "C_C") (pintype "power_in"))
      (node (ref "TP8") (pin "1") (pinfunction "1_1") (pintype "passive"))
      (node (ref "U4") (pin "3") (pinfunction "EN_3") (pintype "passive"))
      (node (ref "U6") (pin "1") (pinfunction "EN/UVLO_1") (pintype "passive"))
    )
    (net (code "20") (name "/ENP") (class "Default")
      (node (ref "R28") (pin "1") (pinfunction "1_1") (pintype "passive"))
      (node (ref "U7") (pin "11") (pinfunction "PA08_D0_11") (pintype "passive"))
    )
    (net (code "21") (name "/FAN_PWM") (class "Default")
      (node (ref "CN4") (pin "1") (pinfunction "1_1") (pintype "passive"))
    )
    (net (code "22") (name "/FAN_TACH") (class "Default")
      (node (ref "CN4") (pin "2") (pinfunction "2_2") (pintype "passive"))
      (node (ref "R38") (pin "2") (pinfunction "2_2") (pintype "passive"))
    )
    (net (code "23") (name "/FAULT") (class "Default")
      (node (ref "R4") (pin "2") (pinfunction "2_2") (pintype "passive"))
      (node (ref "U3") (pin "17") (pinfunction "~{FAULT_IN}_17") (pintype "passive"))
    )
    (net (code "24") (name "/GATE_PPHV") (class "Default")
      (node (ref "Q1") (pin "8") (pinfunction "TR2_GATE_8") (pintype "passive"))
      (node (ref "U3") (pin "20") (pinfunction "GATE_VSYS_20") (pintype "passive"))
    )
    (net (code "25") (name "/GATE_VBUS") (class "Default")
      (node (ref "Q1") (pin "1") (pinfunction "TR1_GATE_1") (pintype "passive"))
      (node (ref "U3") (pin "21") (pinfunction "GATE_VBUS_21") (pintype "passive"))
    )
    (net (code "26") (name "/ISN") (class "Default")
      (node (ref "C42") (pin "2") (pinfunction "2_2") (pintype "passive"))
      (node (ref "R33") (pin "1") (pinfunction "1_1") (pintype "passive"))
      (node (ref "U6") (pin "13") (pinfunction "ISN_13") (pintype "passive"))
    )
    (net (code "27") (name "/ISP") (class "Default")
      (node (ref "C42") (pin "1") (pinfunction "1_1") (pintype "passive"))
      (node (ref "R41") (pin "1") (pinfunction "1_1") (pintype "passive"))
      (node (ref "U6") (pin "12") (pinfunction "ISP_12") (pintype "passive"))
    )
    (net (code "28") (name "/LB") (class "Default")
      (node (ref "R21") (pin "2") (pinfunction "2_2") (pintype "passive"))
      (node (ref "U2") (pin "3") (pinfunction "RESETB_3") (pintype "passive"))
    )
    (net (code "29") (name "/LEDK") (class "Default")
      (node (ref "R31") (pin "1") (pinfunction "1_1") (pintype "passive"))
      (node (ref "U5") (pin "1") (pinfunction "FB_1") (pintype "passive"))
    )
    (net (code "30") (name "/MD_N") (class "Default")
      (node (ref "U7") (pin "23") (pinfunction "PA24_23") (pintype "passive"))
    )
    (net (code "31") (name "/MD_P") (class "Default")
      (node (ref "U7") (pin "24") (pinfunction "PA25_24") (pintype "passive"))
    )
    (net (code "32") (name "/NTC0") (class "Default")
      (node (ref "CN3") (pin "1") (pinfunction "1_1") (pintype "passive"))
      (node (ref "R10") (pin "2") (pinfunction "2_2") (pintype "passive"))
      (node (ref "R19") (pin "1") (pinfunction "1_1") (pintype "passive"))
      (node (ref "U1") (pin "7") (pinfunction "TS_7") (pintype "passive"))
    )
    (net (code "33") (name "/PI_ON") (class "Default")
      (node (ref "TP13") (pin "1") (pinfunction "1_1") (pintype "passive"))
      (node (ref "U7") (pin "12") (pinfunction "PA09_D2_12") (pintype "passive"))
    )
    (net (code "34") (name "/PPHV") (class "Default")
      (node (ref "C10") (pin "1") (pinfunction "1_1") (pintype "passive"))
      (node (ref "C11") (pin "1") (pinfunction "1_1") (pintype "passive"))
      (node (ref "C13") (pin "1") (pinfunction "1_1") (pintype "passive"))
      (node (ref "C20") (pin "1") (pinfunction "1_1") (pintype "passive"))
      (node (ref "D1") (pin "1") (pinfunction "A_1_1") (pintype "passive"))
      (node (ref "D1") (pin "2") (pinfunction "A_2_2") (pintype "passive"))
      (node (ref "D2") (pin "2") (pinfunction "A_2") (pintype "passive"))
      (node (ref "Q1") (pin "5") (pinfunction "TR2_SOURCE_1_5") (pintype "passive"))
      (node (ref "Q1") (pin "6") (pinfunction "TR2_SOURCE_2_6") (pintype "passive"))
      (node (ref "Q1") (pin "7") (pinfunction "TR2_SOURCE_3_7") (pintype "passive"))
      (node (ref "U1") (pin "1") (pinfunction "VBUS_1") (pintype "passive"))
      (node (ref "U3") (pin "19") (pinfunction "VSYS_19") (pintype "passive"))
    )
    (net (code "35") (name "/PWR_BTN") (class "Default")
      (node (ref "SW1") (pin "1") (pinfunction "1_1") (pintype "passive"))
      (node (ref "SW1") (pin "3") (pinfunction "3_3") (pintype "passive"))
      (node (ref "U7") (pin "3") (pinfunction "PA02_D1_3") (pintype "passive"))
    )
    (net (code "36") (name "/REGN") (class "Default")
      (node (ref "C19") (pin "1") (pinfunction "1_1") (pintype "passive"))
      (node (ref "LED2") (pin "1") (pinfunction "A_1") (pintype "passive"))
      (node (ref "R10") (pin "1") (pinfunction "1_1") (pintype "passive"))
      (node (ref "U1") (pin "2") (pinfunction "REGN_2") (pintype "passive"))
    )
    (net (code "37") (name "/RSRV1") (class "Default")
      (node (ref "R12") (pin "1") (pinfunction "1_1") (pintype "passive"))
      (node (ref "U3") (pin "22") (pinfunction "RESERVED_1_22") (pintype "passive"))
    )
    (net (code "38") (name "/RSRV2") (class "Default")
      (node (ref "R13") (pin "1") (pinfunction "1_1") (pintype "passive"))
      (node (ref "U3") (pin "23") (pinfunction "RESERVED_2_23") (pintype "passive"))
    )
    (net (code "39") (name "/RSRV3") (class "Default")
      (node (ref "R14") (pin "1") (pinfunction "1_1") (pintype "passive"))
      (node (ref "U3") (pin "30") (pinfunction "RESERVED_3_30") (pintype "passive"))
    )
    (net (code "40") (name "/SGND") (class "Default")
      (node (ref "C14") (pin "1") (pinfunction "1_1") (pintype "passive"))
      (node (ref "C15") (pin "1") (pinfunction "1_1") (pintype "passive"))
      (node (ref "CN1") (pin "1") (pinfunction "MH1_1") (pintype "passive"))
      (node (ref "CN1") (pin "2") (pinfunction "MH2_2") (pintype "passive"))
      (node (ref "CN1") (pin "3") (pinfunction "MH3_3") (pintype "passive"))
      (node (ref "CN1") (pin "4") (pinfunction "MH4_4") (pintype "passive"))
      (node (ref "R9") (pin "1") (pinfunction "1_1") (pintype "passive"))
    )
    (net (code "41") (name "/STAT") (class "Default")
      (node (ref "R26") (pin "2") (pinfunction "2_2") (pintype "passive"))
      (node (ref "U1") (pin "3") (pinfunction "STAT_3") (pintype "passive"))
    )
    (net (code "42") (name "/SW1") (class "Default")
      (node (ref "C38") (pin "2") (pinfunction "2_2") (pintype "passive"))
      (node (ref "L4") (pin "1") (pinfunction "1_1") (pintype "passive"))
      (node (ref "U6") (pin "8") (pinfunction "SW1_8") (pintype "passive"))
    )
    (net (code "43") (name "/SW2") (class "Default")
      (node (ref "C37") (pin "2") (pinfunction "2_2") (pintype "passive"))
      (node (ref "L4") (pin "2") (pinfunction "2_2") (pintype "passive"))
      (node (ref "U6") (pin "10") (pinfunction "SW2_10") (pintype "passive"))
    )
    (net (code "44") (name "/SWC") (class "Default")
      (node (ref "CN5") (pin "1") (pinfunction "1_1") (pintype "passive"))
      (node (ref "R39") (pin "2") (pinfunction "2_2") (pintype "passive"))
      (node (ref "U7") (pin "31") (pinfunction "PA30_31") (pintype "passive"))
    )
    (net (code "45") (name "/SWD") (class "Default")
      (node (ref "CN5") (pin "2") (pinfunction "2_2") (pintype "passive"))
      (node (ref "U7") (pin "32") (pinfunction "PA31_32") (pintype "passive"))
    )
    (net (code "46") (name "/VBUS") (class "Default")
      (node (ref "C7") (pin "1") (pinfunction "1_1") (pintype "passive"))
      (node (ref "C8") (pin "1") (pinfunction "1_1") (pintype "passive"))
      (node (ref "C9") (pin "1") (pinfunction "1_1") (pintype "passive"))
      (node (ref "F1") (pin "2") (pinfunction "2_2") (pintype "passive"))
      (node (ref "Q1") (pin "2") (pinfunction "TR1_SOURCE_1_2") (pintype "passive"))
      (node (ref "Q1") (pin "3") (pinfunction "TR1_SOURCE_2_3") (pintype "passive"))
      (node (ref "Q1") (pin "4") (pinfunction "TR1_SOURCE_3_4") (pintype "passive"))
      (node (ref "U3") (pin "26") (pinfunction "VBUS_1_26") (pintype "passive"))
      (node (ref "U3") (pin "27") (pinfunction "VBUS_2_27") (pintype "passive"))
    )
    (net (code "47") (name "/VDDA_M") (class "Default")
      (node (ref "C60") (pin "1") (pinfunction "1_1") (pintype "passive"))
      (node (ref "C61") (pin "1") (pinfunction "1_1") (pintype "passive"))
      (node (ref "FB1") (pin "2") (pinfunction "2_2") (pintype "passive"))
      (node (ref "U7") (pin "9") (pinfunction "VDDANA_9") (pintype "passive"))
    )
    (net (code "48") (name "/VIN") (class "Default")
      (node (ref "CN1") (pin "A9") (pinfunction "VBUS_A9") (pintype "passive"))
      (node (ref "CN1") (pin "B9") (pinfunction "VBUS_B9") (pintype "passive"))
      (node (ref "D3") (pin "4") (pinfunction "IN_1_4") (pintype "passive"))
      (node (ref "D3") (pin "5") (pinfunction "IN_2_5") (pintype "passive"))
      (node (ref "D3") (pin "6") (pinfunction "IN_3_6") (pintype "passive"))
      (node (ref "F1") (pin "1") (pinfunction "1_1") (pintype "passive"))
    )
    (net (code "49") (name "/VIN_GATE") (class "Default")
      (node (ref "D2") (pin "1") (pinfunction "K_1_1") (pintype "passive"))
      (node (ref "D2") (pin "3") (pinfunction "K_2_3") (pintype "passive"))
      (node (ref "Q2") (pin "4") (pinfunction "G_4") (pintype "passive"))
      (node (ref "R1") (pin "1") (pinfunction "1_1") (pintype "passive"))
    )
    (net (code "50") (name "AGND") (class "Default")
      (node (ref "C36") (pin "1") (pinfunction "1_1") (pintype "passive"))
      (node (ref "C40") (pin "2") (pinfunction "2_2") (pintype "passive"))
      (node (ref "C43") (pin "2") (pinfunction "2_2") (pintype "passive"))
      (node (ref "NT1") (pin "2") (pintype "passive"))
      (node (ref "R35") (pin "2") (pinfunction "2_2") (pintype "passive"))
      (node (ref "R37") (pin "1") (pinfunction "1_1") (pintype "passive"))
      (node (ref "R43") (pin "2") (pinfunction "2_2") (pintype "passive"))
      (node (ref "U6") (pin "17") (pinfunction "AGND_17") (pintype "passive"))
      (node (ref "U6") (pin "2") (pinfunction "MODE_2") (pintype "passive"))
      (node (ref "U6") (pin "5") (pinfunction "DITH/SYNC_5") (pintype "passive"))
    )
    (net (code "51") (name "GND") (class "Default")
      (node (ref "C10") (pin "2") (pinfunction "2_2") (pintype "passive"))
      (node (ref "C11") (pin "2") (pinfunction "2_2") (pintype "passive"))
      (node (ref "C12") (pin "2") (pinfunction "2_2") (pintype "passive"))
      (node (ref "C13") (pin "2") (pinfunction "2_2") (pintype "passive"))
      (node (ref "C14") (pin "2") (pinfunction "2_2") (pintype "passive"))
      (node (ref "C15") (pin "2") (pinfunction "2_2") (pintype "passive"))
      (node (ref "C16") (pin "2") (pinfunction "2_2") (pintype "passive"))
      (node (ref "C17") (pin "2") (pinfunction "2_2") (pintype "passive"))
      (node (ref "C18") (pin "2") (pinfunction "2_2") (pintype "passive"))
      (node (ref "C19") (pin "2") (pinfunction "2_2") (pintype "passive"))
      (node (ref "C2") (pin "2") (pinfunction "2_2") (pintype "passive"))
      (node (ref "C20") (pin "2") (pinfunction "2_2") (pintype "passive"))
      (node (ref "C21") (pin "2") (pinfunction "2_2") (pintype "passive"))
      (node (ref "C22") (pin "2") (pinfunction "2_2") (pintype "passive"))
      (node (ref "C23") (pin "2") (pinfunction "2_2") (pintype "passive"))
      (node (ref "C24") (pin "2") (pinfunction "2_2") (pintype "passive"))
      (node (ref "C25") (pin "2") (pinfunction "2_2") (pintype "passive"))
      (node (ref "C26") (pin "2") (pinfunction "2_2") (pintype "passive"))
      (node (ref "C27") (pin "2") (pinfunction "2_2") (pintype "passive"))
      (node (ref "C28") (pin "2") (pinfunction "2_2") (pintype "passive"))
      (node (ref "C29") (pin "2") (pinfunction "2_2") (pintype "passive"))
      (node (ref "C3") (pin "2") (pinfunction "2_2") (pintype "passive"))
      (node (ref "C30") (pin "2") (pinfunction "2_2") (pintype "passive"))
      (node (ref "C31") (pin "2") (pinfunction "2_2") (pintype "passive"))
      (node (ref "C32") (pin "2") (pinfunction "2_2") (pintype "passive"))
      (node (ref "C33") (pin "2") (pinfunction "2_2") (pintype "passive"))
      (node (ref "C34") (pin "2") (pinfunction "2_2") (pintype "passive"))
      (node (ref "C35") (pin "2") (pinfunction "2_2") (pintype "passive"))
      (node (ref "C39") (pin "2") (pinfunction "2_2") (pintype "passive"))
      (node (ref "C4") (pin "2") (pinfunction "2_2") (pintype "passive"))
      (node (ref "C41") (pin "2") (pinfunction "2_2") (pintype "passive"))
      (node (ref "C44") (pin "2") (pinfunction "2_2") (pintype "passive"))
      (node (ref "C45") (pin "2") (pinfunction "2_2") (pintype "passive"))
      (node (ref "C46") (pin "2") (pinfunction "2_2") (pintype "passive"))
      (node (ref "C47") (pin "2") (pinfunction "2_2") (pintype "passive"))
      (node (ref "C48") (pin "2") (pinfunction "2_2") (pintype "passive"))
      (node (ref "C49") (pin "2") (pinfunction "2_2") (pintype "passive"))
      (node (ref "C5") (pin "2") (pinfunction "2_2") (pintype "passive"))
      (node (ref "C50") (pin "2") (pinfunction "2_2") (pintype "passive"))
      (node (ref "C51") (pin "2") (pinfunction "2_2") (pintype "passive"))
      (node (ref "C52") (pin "2") (pinfunction "2_2") (pintype "passive"))
      (node (ref "C53") (pin "2") (pinfunction "2_2") (pintype "passive"))
      (node (ref "C54") (pin "2") (pinfunction "-_2") (pintype "passive"))
      (node (ref "C55") (pin "2") (pinfunction "2_2") (pintype "passive"))
      (node (ref "C56") (pin "2") (pinfunction "2_2") (pintype "passive"))
      (node (ref "C57") (pin "2") (pinfunction "2_2") (pintype "passive"))
      (node (ref "C58") (pin "2") (pinfunction "2_2") (pintype "passive"))
      (node (ref "C59") (pin "2") (pinfunction "2_2") (pintype "passive"))
      (node (ref "C6") (pin "2") (pinfunction "2_2") (pintype "passive"))
      (node (ref "C60") (pin "2") (pinfunction "2_2") (pintype "passive"))
      (node (ref "C61") (pin "2") (pinfunction "2_2") (pintype "passive"))
      (node (ref "C62") (pin "2") (pinfunction "2_2") (pintype "passive"))
      (node (ref "C7") (pin "2") (pinfunction "2_2") (pintype "passive"))
      (node (ref "C8") (pin "2") (pinfunction "2_2") (pintype "passive"))
      (node (ref "C9") (pin "2") (pinfunction "2_2") (pintype "passive"))
      (node (ref "CN1") (pin "A12") (pinfunction "GND_A12") (pintype "passive"))
      (node (ref "CN1") (pin "B12") (pinfunction "GND_B12") (pintype "passive"))
      (node (ref "CN2") (pin "2") (pinfunction "GND_2") (pintype "power_in"))
      (node (ref "CN3") (pin "2") (pinfunction "2_2") (pintype "passive"))
      (node (ref "CN3") (pin "3") (pinfunction "MNT_1_3") (pintype "passive"))
      (node (ref "CN3") (pin "4") (pinfunction "MNT_2_4") (pintype "passive"))
      (node (ref "CN4") (pin "3") (pinfunction "3_3") (pintype "passive"))
      (node (ref "CN4") (pin "5") (pinfunction "MNT_1_5") (pintype "passive"))
      (node (ref "CN4") (pin "6") (pinfunction "MNT_2_6") (pintype "passive"))
      (node (ref "CN5") (pin "4") (pinfunction "4_4") (pintype "passive"))
      (node (ref "CN5") (pin "5") (pinfunction "MNT_1_5") (pintype "passive"))
      (node (ref "CN5") (pin "6") (pinfunction "MNT_2_6") (pintype "passive"))
      (node (ref "D3") (pin "1") (pinfunction "GND_1_1") (pintype "passive"))
      (node (ref "D3") (pin "2") (pinfunction "GND_2_2") (pintype "passive"))
      (node (ref "D3") (pin "3") (pinfunction "GND_3_3") (pintype "passive"))
      (node (ref "D3") (pin "7") (pinfunction "EP_7") (pintype "passive"))
      (node (ref "LED3") (pin "6") (pinfunction "GND_6") (pintype "passive"))
      (node (ref "LED3") (pin "8") (pinfunction "GND_8") (pintype "passive"))
      (node (ref "LED4") (pin "2") (pinfunction "K_2") (pintype "passive"))
      (node (ref "NT1") (pin "1") (pintype "passive"))
      (node (ref "Q3") (pin "2") (pinfunction "E_2") (pintype "passive"))
      (node (ref "Q4") (pin "3") (pinfunction "S_3") (pintype "passive"))
      (node (ref "Q4") (pin "4") (pinfunction "S_4") (pintype "passive"))
      (node (ref "Q5") (pin "3") (pinfunction "S_3") (pintype "passive"))
      (node (ref "Q5") (pin "4") (pinfunction "S_4") (pintype "passive"))
      (node (ref "Q6") (pin "3") (pinfunction "S_3") (pintype "passive"))
      (node (ref "Q6") (pin "4") (pinfunction "S_4") (pintype "passive"))
      (node (ref "R1") (pin "2") (pinfunction "2_2") (pintype "passive"))
      (node (ref "R12") (pin "2") (pinfunction "2_2") (pintype "passive"))
      (node (ref "R13") (pin "2") (pinfunction "2_2") (pintype "passive"))
      (node (ref "R14") (pin "2") (pinfunction "2_2") (pintype "passive"))
      (node (ref "R15") (pin "2") (pinfunction "2_2") (pintype "passive"))
      (node (ref "R16") (pin "2") (pinfunction "2_2") (pintype "passive"))
      (node (ref "R17") (pin "2") (pinfunction "2_2") (pintype "passive"))
      (node (ref "R18") (pin "2") (pinfunction "2_2") (pintype "passive"))
      (node (ref "R19") (pin "2") (pinfunction "2_2") (pintype "passive"))
      (node (ref "R2") (pin "2") (pinfunction "2_2") (pintype "passive"))
      (node (ref "R20") (pin "2") (pinfunction "2_2") (pintype "passive"))
      (node (ref "R27") (pin "1") (pinfunction "1_1") (pintype "passive"))
      (node (ref "R29") (pin "2") (pinfunction "2_2") (pintype "passive"))
      (node (ref "R3") (pin "2") (pinfunction "2_2") (pintype "passive"))
      (node (ref "R30") (pin "2") (pinfunction "2_2") (pintype "passive"))
      (node (ref "R31") (pin "2") (pinfunction "2_2") (pintype "passive"))
      (node (ref "R32") (pin "2") (pinfunction "2_2") (pintype "passive"))
      (node (ref "R9") (pin "2") (pinfunction "2_2") (pintype "passive"))
      (node (ref "SW1") (pin "2") (pinfunction "2_2") (pintype "passive"))
      (node (ref "SW1") (pin "4") (pinfunction "4_4") (pintype "passive"))
      (node (ref "SW2") (pin "3") (pinfunction "NC_3") (pintype "power_in"))
      (node (ref "SW2") (pin "4") (pinfunction "4_4") (pintype "power_in"))
      (node (ref "SW3") (pin "1") (pinfunction "1_1") (pintype "passive"))
      (node (ref "TP4") (pin "1") (pinfunction "1_1") (pintype "passive"))
      (node (ref "TP5") (pin "1") (pinfunction "1_1") (pintype "passive"))
      (node (ref "U1") (pin "11") (pinfunction "GND_1_11") (pintype "passive"))
      (node (ref "U1") (pin "12") (pinfunction "GND_2_12") (pintype "passive"))
      (node (ref "U1") (pin "17") (pinfunction "EP_17") (pintype "passive"))
      (node (ref "U1") (pin "6") (pinfunction "~{EN}_6") (pintype "passive"))
      (node (ref "U10") (pin "10") (pinfunction "0P4V_10") (pintype "passive"))
      (node (ref "U10") (pin "11") (pinfunction "0P2V_11") (pintype "passive"))
      (node (ref "U10") (pin "12") (pinfunction "0P1V_12") (pintype "passive"))
      (node (ref "U10") (pin "21") (pinfunction "GND_2_21") (pintype "passive"))
      (node (ref "U10") (pin "7") (pinfunction "GND_1_7") (pintype "passive"))
      (node (ref "U10") (pin "8") (pinfunction "1P6V_8") (pintype "passive"))
      (node (ref "U10") (pin "9") (pinfunction "0P8V_9") (pintype "passive"))
      (node (ref "U2") (pin "2") (pinfunction "VSS_2") (pintype "passive"))
      (node (ref "U3") (pin "11") (pinfunction "GND_1_11") (pintype "passive"))
      (node (ref "U3") (pin "12") (pinfunction "GND_2_12") (pintype "passive"))
      (node (ref "U3") (pin "14") (pinfunction "GND_3_14") (pintype "passive"))
      (node (ref "U3") (pin "15") (pinfunction "GND_4_15") (pintype "passive"))
      (node (ref "U3") (pin "16") (pinfunction "GND_5_16") (pintype "passive"))
      (node (ref "U3") (pin "28") (pinfunction "GND_6_28") (pintype "passive"))
      (node (ref "U3") (pin "29") (pinfunction "GND_7_29") (pintype "passive"))
      (node (ref "U3") (pin "33") (pinfunction "GND_8_33") (pintype "passive"))
      (node (ref "U3") (pin "8") (pinfunction "I2CT_SDA_8") (pintype "passive"))
      (node (ref "U3") (pin "9") (pinfunction "I2CT_SCL_9") (pintype "passive"))
      (node (ref "U4") (pin "11") (pinfunction "EP_11") (pintype "passive"))
      (node (ref "U4") (pin "4") (pinfunction "PS/SYNC_4") (pintype "passive"))
      (node (ref "U4") (pin "7") (pinfunction "GND_7") (pintype "passive"))
      (node (ref "U5") (pin "3") (pinfunction "GND_3") (pintype "power_in"))
      (node (ref "U5") (pin "7") (pinfunction "EP_7") (pintype "power_in"))
      (node (ref "U6") (pin "22") (pinfunction "PGND_2_22") (pintype "passive"))
      (node (ref "U6") (pin "23") (pinfunction "PGND_3_23") (pintype "passive"))
      (node (ref "U6") (pin "9") (pinfunction "PGND_1_9") (pintype "passive"))
      (node (ref "U7") (pin "10") (pinfunction "GND_1_10") (pintype "passive"))
      (node (ref "U7") (pin "28") (pinfunction "GND_2_28") (pintype "passive"))
      (node (ref "U7") (pin "33") (pinfunction "EP_33") (pintype "passive"))
      (node (ref "U8") (pin "3") (pinfunction "GND_3") (pintype "power_in"))
      (node (ref "U8") (pin "7") (pinfunction "Thermal_Pad_7") (pintype "power_in"))
      (node (ref "U9") (pin "2") (pinfunction "VSS_2") (pintype "passive"))
    )
    (net (code "52") (name "LDO_1V5") (class "Default")
      (node (ref "C18") (pin "1") (pinfunction "1_1") (pintype "passive"))
      (node (ref "U3") (pin "4") (pinfunction "LDO_1V5_4") (pintype "passive"))
    )
    (net (code "53") (name "LDO_3V3") (class "Default")
      (node (ref "C17") (pin "1") (pinfunction "1_1") (pintype "passive"))
      (node (ref "R4") (pin "1") (pinfunction "1_1") (pintype "passive"))
      (node (ref "R5") (pin "1") (pinfunction "1_1") (pintype "passive"))
      (node (ref "R6") (pin "1") (pinfunction "1_1") (pintype "passive"))
      (node (ref "R7") (pin "1") (pinfunction "1_1") (pintype "passive"))
      (node (ref "R8") (pin "1") (pinfunction "1_1") (pintype "passive"))
      (node (ref "U3") (pin "1") (pinfunction "LDO_3V3_1") (pintype "passive"))
    )
    (net (code "54") (name "Net-(C40-Pad1)") (class "Default")
      (node (ref "C40") (pin "1") (pinfunction "1_1") (pintype "passive"))
      (node (ref "R36") (pin "2") (pinfunction "2_2") (pintype "passive"))
    )
    (net (code "55") (name "Net-(LED1-K)") (class "Default")
      (node (ref "LED1") (pin "2") (pinfunction "K_2") (pintype "passive"))
      (node (ref "R21") (pin "1") (pinfunction "1_1") (pintype "passive"))
    )
    (net (code "56") (name "Net-(LED2-K)") (class "Default")
      (node (ref "LED2") (pin "2") (pinfunction "K_2") (pintype "passive"))
      (node (ref "R26") (pin "1") (pinfunction "1_1") (pintype "passive"))
    )
    (net (code "57") (name "Net-(LED3-VDD-Pad1)") (class "Default")
      (node (ref "LED3") (pin "1") (pinfunction "VDD_1") (pintype "passive"))
      (node (ref "LED3") (pin "7") (pinfunction "VDD_7") (pintype "passive"))
      (node (ref "R44") (pin "2") (pinfunction "2_2") (pintype "passive"))
    )
    (net (code "58") (name "Net-(LED4-A)") (class "Default")
      (node (ref "LED4") (pin "1") (pinfunction "A_1") (pintype "passive"))
      (node (ref "R46") (pin "2") (pinfunction "2_2") (pintype "passive"))
    )
    (net (code "59") (name "Net-(Q3-B)") (class "Default")
      (node (ref "Q3") (pin "1") (pinfunction "B_1") (pintype "passive"))
      (node (ref "R28") (pin "2") (pinfunction "2_2") (pintype "passive"))
    )
    (net (code "60") (name "Net-(Q4-D)") (class "Default")
      (node (ref "Q4") (pin "1") (pinfunction "D_1") (pintype "passive"))
      (node (ref "Q6") (pin "1") (pinfunction "D_1") (pintype "passive"))
      (node (ref "R24") (pin "2") (pinfunction "2_2") (pintype "passive"))
      (node (ref "U5") (pin "5") (pinfunction "CTRL_5") (pintype "input"))
    )
    (net (code "61") (name "Net-(Q5-D)") (class "Default")
      (node (ref "Q5") (pin "1") (pinfunction "D_1") (pintype "passive"))
      (node (ref "Q6") (pin "2") (pinfunction "G_2") (pintype "passive"))
      (node (ref "R23") (pin "2") (pinfunction "2_2") (pintype "passive"))
    )
    (net (code "62") (name "Net-(R22-Pad2)") (class "Default")
      (node (ref "R22") (pin "2") (pinfunction "2_2") (pintype "passive"))
      (node (ref "SW2") (pin "1") (pinfunction "1_1") (pintype "power_in"))
    )
    (net (code "63") (name "Net-(R30-Pad1)") (class "Default")
      (node (ref "R30") (pin "1") (pinfunction "1_1") (pintype "passive"))
      (node (ref "SW2") (pin "2") (pinfunction "2_2") (pintype "passive"))
    )
    (net (code "64") (name "Net-(R42-Pad2)") (class "Default")
      (node (ref "R42") (pin "2") (pinfunction "2_2") (pintype "passive"))
      (node (ref "SW3") (pin "2") (pinfunction "2_2") (pintype "passive"))
    )
    (net (code "65") (name "Net-(U1-BTST)") (class "Default")
      (node (ref "C1") (pin "1") (pinfunction "1_1") (pintype "passive"))
      (node (ref "U1") (pin "15") (pinfunction "BTST_15") (pintype "passive"))
    )
    (net (code "66") (name "Net-(U1-ICHG)") (class "Default")
      (node (ref "R2") (pin "1") (pinfunction "1_1") (pintype "passive"))
      (node (ref "U1") (pin "4") (pinfunction "ICHG_4") (pintype "passive"))
    )
    (net (code "67") (name "Net-(U1-PMID)") (class "Default")
      (node (ref "C6") (pin "1") (pinfunction "1_1") (pintype "passive"))
      (node (ref "U1") (pin "16") (pinfunction "PMID_16") (pintype "passive"))
    )
    (net (code "68") (name "Net-(U1-SW_1)") (class "Default")
      (node (ref "C1") (pin "2") (pinfunction "2_2") (pintype "passive"))
      (node (ref "L1") (pin "1") (pinfunction "1_1") (pintype "passive"))
      (node (ref "U1") (pin "13") (pinfunction "SW_1_13") (pintype "passive"))
      (node (ref "U1") (pin "14") (pinfunction "SW_2_14") (pintype "passive"))
    )
    (net (code "69") (name "Net-(U1-VSET)") (class "Default")
      (node (ref "R3") (pin "1") (pinfunction "1_1") (pintype "passive"))
      (node (ref "U1") (pin "9") (pinfunction "VSET_9") (pintype "passive"))
    )
    (net (code "70") (name "Net-(U4-FB)") (class "Default")
      (node (ref "C30") (pin "1") (pinfunction "1_1") (pintype "passive"))
      (node (ref "R25") (pin "2") (pinfunction "2_2") (pintype "passive"))
      (node (ref "R29") (pin "1") (pinfunction "1_1") (pintype "passive"))
      (node (ref "U4") (pin "8") (pinfunction "FB_8") (pintype "passive"))
    )
    (net (code "71") (name "Net-(U4-L1)") (class "Default")
      (node (ref "L2") (pin "1") (pinfunction "1_1") (pintype "passive"))
      (node (ref "U4") (pin "1") (pinfunction "L1_1") (pintype "passive"))
    )
    (net (code "72") (name "Net-(U4-L2)") (class "Default")
      (node (ref "L2") (pin "2") (pinfunction "2_2") (pintype "passive"))
      (node (ref "U4") (pin "10") (pinfunction "L2_10") (pintype "passive"))
    )
    (net (code "73") (name "Net-(U4-VAUX)") (class "Default")
      (node (ref "C29") (pin "1") (pinfunction "1_1") (pintype "passive"))
      (node (ref "U4") (pin "6") (pinfunction "VAUX_6") (pintype "passive"))
    )
    (net (code "74") (name "Net-(U5-COMP)") (class "Default")
      (node (ref "C32") (pin "1") (pinfunction "1_1") (pintype "passive"))
      (node (ref "U5") (pin "2") (pinfunction "COMP_2") (pintype "passive"))
    )
    (net (code "75") (name "Net-(U5-SW)") (class "Default")
      (node (ref "D4") (pin "2") (pinfunction "2_2") (pintype "passive"))
      (node (ref "L3") (pin "2") (pinfunction "2_2") (pintype "passive"))
      (node (ref "U5") (pin "4") (pinfunction "SW_4") (pintype "power_in"))
    )
    (net (code "76") (name "Net-(U6-BOOT1)") (class "Default")
      (node (ref "C38") (pin "1") (pinfunction "1_1") (pintype "passive"))
      (node (ref "U6") (pin "20") (pinfunction "BOOT1_20") (pintype "passive"))
    )
    (net (code "77") (name "Net-(U6-BOOT2)") (class "Default")
      (node (ref "C37") (pin "1") (pinfunction "1_1") (pintype "passive"))
      (node (ref "U6") (pin "19") (pinfunction "BOOT2_19") (pintype "passive"))
    )
    (net (code "78") (name "Net-(U6-CDC)") (class "Default")
      (node (ref "R35") (pin "1") (pinfunction "1_1") (pintype "passive"))
      (node (ref "U6") (pin "16") (pinfunction "CDC_16") (pintype "passive"))
    )
    (net (code "79") (name "Net-(U6-COMP)") (class "Default")
      (node (ref "C36") (pin "2") (pinfunction "2_2") (pintype "passive"))
      (node (ref "R36") (pin "1") (pinfunction "1_1") (pintype "passive"))
      (node (ref "U6") (pin "15") (pinfunction "COMP_15") (pintype "passive"))
    )
    (net (code "80") (name "Net-(U6-EXTVCC)") (class "Default")
      (node (ref "C39") (pin "1") (pinfunction "1_1") (pintype "passive"))
      (node (ref "C43") (pin "1") (pinfunction "1_1") (pintype "passive"))
      (node (ref "U6") (pin "18") (pinfunction "VCC_18") (pintype "passive"))
      (node (ref "U6") (pin "21") (pinfunction "EXTVCC_21") (pintype "passive"))
    )
    (net (code "81") (name "Net-(U6-FB)") (class "Default")
      (node (ref "R34") (pin "2") (pinfunction "2_2") (pintype "passive"))
      (node (ref "R37") (pin "2") (pinfunction "2_2") (pintype "passive"))
      (node (ref "U6") (pin "14") (pinfunction "FB_14") (pintype "passive"))
    )
    (net (code "82") (name "Net-(U6-FSW)") (class "Default")
      (node (ref "R43") (pin "1") (pinfunction "1_1") (pintype "passive"))
      (node (ref "U6") (pin "6") (pinfunction "FSW_6") (pintype "passive"))
    )
    (net (code "83") (name "Net-(U7-PA10)") (class "Default")
      (node (ref "R46") (pin "1") (pinfunction "1_1") (pintype "passive"))
      (node (ref "U7") (pin "13") (pinfunction "PA10_13") (pintype "passive"))
    )
    (net (code "84") (name "Net-(U7-VDDCORE)") (class "Default")
      (node (ref "C41") (pin "1") (pinfunction "1_1") (pintype "passive"))
      (node (ref "U7") (pin "29") (pinfunction "VDDCORE_29") (pintype "passive"))
    )
    (net (code "85") (name "Net-(U7-~{RESET})") (class "Default")
      (node (ref "C50") (pin "1") (pinfunction "1_1") (pintype "passive"))
      (node (ref "R42") (pin "1") (pinfunction "1_1") (pintype "passive"))
      (node (ref "U7") (pin "26") (pinfunction "~{RESET}_26") (pintype "passive"))
    )
    (net (code "86") (name "Net-(U10-NR)") (class "Default")
      (node (ref "C55") (pin "1") (pinfunction "1_1") (pintype "passive"))
      (node (ref "U10") (pin "14") (pinfunction "NR_14") (pintype "passive"))
    )
    (net (code "87") (name "VBAT") (class "Default")
      (node (ref "C21") (pin "1") (pinfunction "1_1") (pintype "passive"))
      (node (ref "C3") (pin "1") (pinfunction "1_1") (pintype "passive"))
      (node (ref "C62") (pin "1") (pinfunction "1_1") (pintype "passive"))
      (node (ref "CN2") (pin "1") (pinfunction "VBAT_1") (pintype "power_in"))
      (node (ref "L1") (pin "2") (pinfunction "2_2") (pintype "passive"))
      (node (ref "Q2") (pin "5") (pinfunction "D_1_5") (pintype "passive"))
      (node (ref "Q2") (pin "6") (pinfunction "D_2_6") (pintype "passive"))
      (node (ref "Q2") (pin "7") (pinfunction "D_3_7") (pintype "passive"))
      (node (ref "Q2") (pin "8") (pinfunction "D_4_8") (pintype "passive"))
      (node (ref "R11") (pin "1") (pinfunction "1_1") (pintype "passive"))
      (node (ref "TP2") (pin "1") (pinfunction "1_1") (pintype "passive"))
      (node (ref "TP3") (pin "1") (pinfunction "1_1") (pintype "passive"))
      (node (ref "U1") (pin "10") (pinfunction "BAT_10") (pintype "passive"))
      (node (ref "U2") (pin "4") (pinfunction "VIN_4") (pintype "passive"))
      (node (ref "U9") (pin "1") (pinfunction "VIN_1") (pintype "passive"))
      (node (ref "U9") (pin "3") (pinfunction "CE_3") (pintype "passive"))
    )
    (net (code "88") (name "VIN_3V3") (class "Default")
      (node (ref "C16") (pin "1") (pinfunction "1_1") (pintype "passive"))
      (node (ref "U3") (pin "32") (pinfunction "VIN_3V3_32") (pintype "passive"))
    )
    (net (code "89") (name "VOUT") (class "Default")
      (node (ref "C45") (pin "1") (pinfunction "1_1") (pintype "passive"))
      (node (ref "C46") (pin "1") (pinfunction "1_1") (pintype "passive"))
      (node (ref "C47") (pin "1") (pinfunction "1_1") (pintype "passive"))
      (node (ref "R40") (pin "2") (pinfunction "2_2") (pintype "passive"))
      (node (ref "R41") (pin "2") (pinfunction "2_2") (pintype "passive"))
      (node (ref "U6") (pin "11") (pinfunction "VOUT_11") (pintype "passive"))
    )
    (net (code "90") (name "VSYS") (class "Default")
      (node (ref "C24") (pin "1") (pinfunction "1_1") (pintype "passive"))
      (node (ref "C25") (pin "1") (pinfunction "1_1") (pintype "passive"))
      (node (ref "C33") (pin "1") (pinfunction "1_1") (pintype "passive"))
      (node (ref "C34") (pin "1") (pinfunction "1_1") (pintype "passive"))
      (node (ref "C35") (pin "1") (pinfunction "1_1") (pintype "passive"))
      (node (ref "C4") (pin "1") (pinfunction "1_1") (pintype "passive"))
      (node (ref "C5") (pin "1") (pinfunction "1_1") (pintype "passive"))
      (node (ref "D1") (pin "3") (pinfunction "K_3") (pintype "passive"))
      (node (ref "Q2") (pin "1") (pinfunction "S_1_1") (pintype "passive"))
      (node (ref "Q2") (pin "2") (pinfunction "S_2_2") (pintype "passive"))
      (node (ref "Q2") (pin "3") (pinfunction "S_3_3") (pintype "passive"))
      (node (ref "TP1") (pin "1") (pinfunction "1_1") (pintype "passive"))
      (node (ref "U4") (pin "2") (pinfunction "VIN_2") (pintype "passive"))
      (node (ref "U6") (pin "7") (pinfunction "VIN_7") (pintype "passive"))
    )
    (net (code "91") (name "unconnected-(CN2-NC-Pad4)") (class "Default")
      (node (ref "CN2") (pin "4") (pinfunction "NC_4") (pintype "power_in+no_connect"))
    )
    (net (code "92") (name "unconnected-(CN2-NTC-Pad3)") (class "Default")
      (node (ref "CN2") (pin "3") (pinfunction "NTC_3") (pintype "output+no_connect"))
    )
    (net (code "93") (name "unconnected-(LED3-CK0-Pad2)") (class "Default")
      (node (ref "LED3") (pin "2") (pinfunction "CK0_2") (pintype "passive+no_connect"))
    )
    (net (code "94") (name "unconnected-(LED3-SD0-Pad3)") (class "Default")
      (node (ref "LED3") (pin "3") (pinfunction "SD0_3") (pintype "passive+no_connect"))
    )
    (net (code "95") (name "unconnected-(Q1-TR1_DRAIN{slash}TR2_DRAIN-Pad9)") (class "Default")
      (node (ref "Q1") (pin "9") (pinfunction "TR1_DRAIN/TR2_DRAIN_9") (pintype "passive+no_connect"))
    )
    (net (code "96") (name "unconnected-(U1-NC-Pad8)") (class "Default")
      (node (ref "U1") (pin "8") (pinfunction "NC_8") (pintype "passive+no_connect"))
    )
    (net (code "97") (name "unconnected-(U1-POL-Pad5)") (class "Default")
      (node (ref "U1") (pin "5") (pinfunction "POL_5") (pintype "passive+no_connect"))
    )
    (net (code "98") (name "unconnected-(U2-NC-Pad1)") (class "Default")
      (node (ref "U2") (pin "1") (pinfunction "NC_1") (pintype "passive+no_connect"))
    )
    (net (code "99") (name "unconnected-(U3-CAP_MIS-Pad6)") (class "Default")
      (node (ref "U3") (pin "6") (pinfunction "CAP_MIS_6") (pintype "passive+no_connect"))
    )
    (net (code "100") (name "unconnected-(U3-DBG_ACC-Pad10)") (class "Default")
      (node (ref "U3") (pin "10") (pinfunction "DBG_ACC_10") (pintype "passive+no_connect"))
    )
    (net (code "101") (name "unconnected-(U3-PLUG_EVENT-Pad31)") (class "Default")
      (node (ref "U3") (pin "31") (pinfunction "PLUG_EVENT_31") (pintype "passive+no_connect"))
    )
    (net (code "102") (name "unconnected-(U3-PLUG_FLIP-Pad13)") (class "Default")
      (node (ref "U3") (pin "13") (pinfunction "PLUG_FLIP_13") (pintype "passive+no_connect"))
    )
    (net (code "103") (name "unconnected-(U3-~{SINK_EN}-Pad18)") (class "Default")
      (node (ref "U3") (pin "18") (pinfunction "~{SINK_EN}_18") (pintype "passive+no_connect"))
    )
    (net (code "104") (name "unconnected-(U4-PG-Pad5)") (class "Default")
      (node (ref "U4") (pin "5") (pinfunction "PG_5") (pintype "passive+no_connect"))
    )
    (net (code "105") (name "unconnected-(U6-PG-Pad3)") (class "Default")
      (node (ref "U6") (pin "3") (pinfunction "PG_3") (pintype "passive+no_connect"))
    )
    (net (code "106") (name "unconnected-(U6-~{CC}-Pad4)") (class "Default")
      (node (ref "U6") (pin "4") (pinfunction "~{CC}_4") (pintype "passive+no_connect"))
    )
    (net (code "107") (name "unconnected-(U7-PA03-Pad4)") (class "Default")
      (node (ref "U7") (pin "4") (pinfunction "PA03_4") (pintype "passive+no_connect"))
    )
    (net (code "108") (name "unconnected-(U7-PA04-Pad5)") (class "Default")
      (node (ref "U7") (pin "5") (pinfunction "PA04_5") (pintype "passive+no_connect"))
    )
    (net (code "109") (name "unconnected-(U7-PA05-Pad6)") (class "Default")
      (node (ref "U7") (pin "6") (pinfunction "PA05_6") (pintype "passive+no_connect"))
    )
    (net (code "110") (name "unconnected-(U7-PA11-Pad14)") (class "Default")
      (node (ref "U7") (pin "14") (pinfunction "PA11_14") (pintype "passive+no_connect"))
    )
    (net (code "111") (name "unconnected-(U7-PA14-Pad15)") (class "Default")
      (node (ref "U7") (pin "15") (pinfunction "PA14_15") (pintype "passive+no_connect"))
    )
    (net (code "112") (name "unconnected-(U7-PA15-Pad16)") (class "Default")
      (node (ref "U7") (pin "16") (pinfunction "PA15_16") (pintype "passive+no_connect"))
    )
    (net (code "113") (name "unconnected-(U7-PA16-Pad17)") (class "Default")
      (node (ref "U7") (pin "17") (pinfunction "PA16_17") (pintype "passive+no_connect"))
    )
    (net (code "114") (name "unconnected-(U7-PA17-Pad18)") (class "Default")
      (node (ref "U7") (pin "18") (pinfunction "PA17_18") (pintype "passive+no_connect"))
    )
    (net (code "115") (name "unconnected-(U7-PA18-Pad19)") (class "Default")
      (node (ref "U7") (pin "19") (pinfunction "PA18_19") (pintype "passive+no_connect"))
    )
    (net (code "116") (name "unconnected-(U7-PA19-Pad20)") (class "Default")
      (node (ref "U7") (pin "20") (pinfunction "PA19_20") (pintype "passive+no_connect"))
    )
    (net (code "117") (name "unconnected-(U7-PA22-Pad21)") (class "Default")
      (node (ref "U7") (pin "21") (pinfunction "PA22_21") (pintype "passive+no_connect"))
    )
    (net (code "118") (name "unconnected-(U7-PA23-Pad22)") (class "Default")
      (node (ref "U7") (pin "22") (pinfunction "PA23_22") (pintype "passive+no_connect"))
    )
    (net (code "119") (name "unconnected-(U7-PA27-Pad25)") (class "Default")
      (node (ref "U7") (pin "25") (pinfunction "PA27_25") (pintype "passive+no_connect"))
    )
    (net (code "120") (name "unconnected-(U7-PA28-Pad27)") (class "Default")
      (node (ref "U7") (pin "27") (pinfunction "PA28_27") (pintype "passive+no_connect"))
    )
    (net (code "121") (name "unconnected-(U8-NC-Pad2)") (class "Default")
      (node (ref "U8") (pin "2") (pinfunction "NC_2") (pintype "passive+no_connect"))
    )
    (net (code "122") (name "unconnected-(U8-NC-Pad5)") (class "Default")
      (node (ref "U8") (pin "5") (pinfunction "NC_5") (pintype "passive+no_connect"))
    )
    (net (code "123") (name "unconnected-(U9-NC-Pad4)") (class "Default")
      (node (ref "U9") (pin "4") (pinfunction "NC_4") (pintype "passive+no_connect"))
    )
    (net (code "124") (name "unconnected-(U10-3P2V-Pad6)") (class "Default")
      (node (ref "U10") (pin "6") (pinfunction "3P2V_6") (pintype "passive+no_connect"))
    )
    (net (code "125") (name "unconnected-(U10-6P4V1-Pad5)") (class "Default")
      (node (ref "U10") (pin "5") (pinfunction "6P4V1_5") (pintype "passive+no_connect"))
    )
    (net (code "126") (name "unconnected-(U10-6P4V2-Pad4)") (class "Default")
      (node (ref "U10") (pin "4") (pinfunction "6P4V2_4") (pintype "passive+no_connect"))
    )
    (net (code "127") (name "unconnected-(U10-NC_1-Pad2)") (class "Default")
      (node (ref "U10") (pin "2") (pinfunction "NC_1_2") (pintype "passive+no_connect"))
    )
    (net (code "128") (name "unconnected-(U10-NC_2-Pad17)") (class "Default")
      (node (ref "U10") (pin "17") (pinfunction "NC_2_17") (pintype "passive+no_connect"))
    )
    (net (code "129") (name "unconnected-(U10-NC_3-Pad18)") (class "Default")
      (node (ref "U10") (pin "18") (pinfunction "NC_3_18") (pintype "passive+no_connect"))
    )
    (net (code "130") (name "unconnected-(U10-NC_4-Pad19)") (class "Default")
      (node (ref "U10") (pin "19") (pinfunction "NC_4_19") (pintype "passive+no_connect"))
    )
  )
)
